# TicTacToe_v3.net
KiCad netlist of a schematic drawn in EAGLE
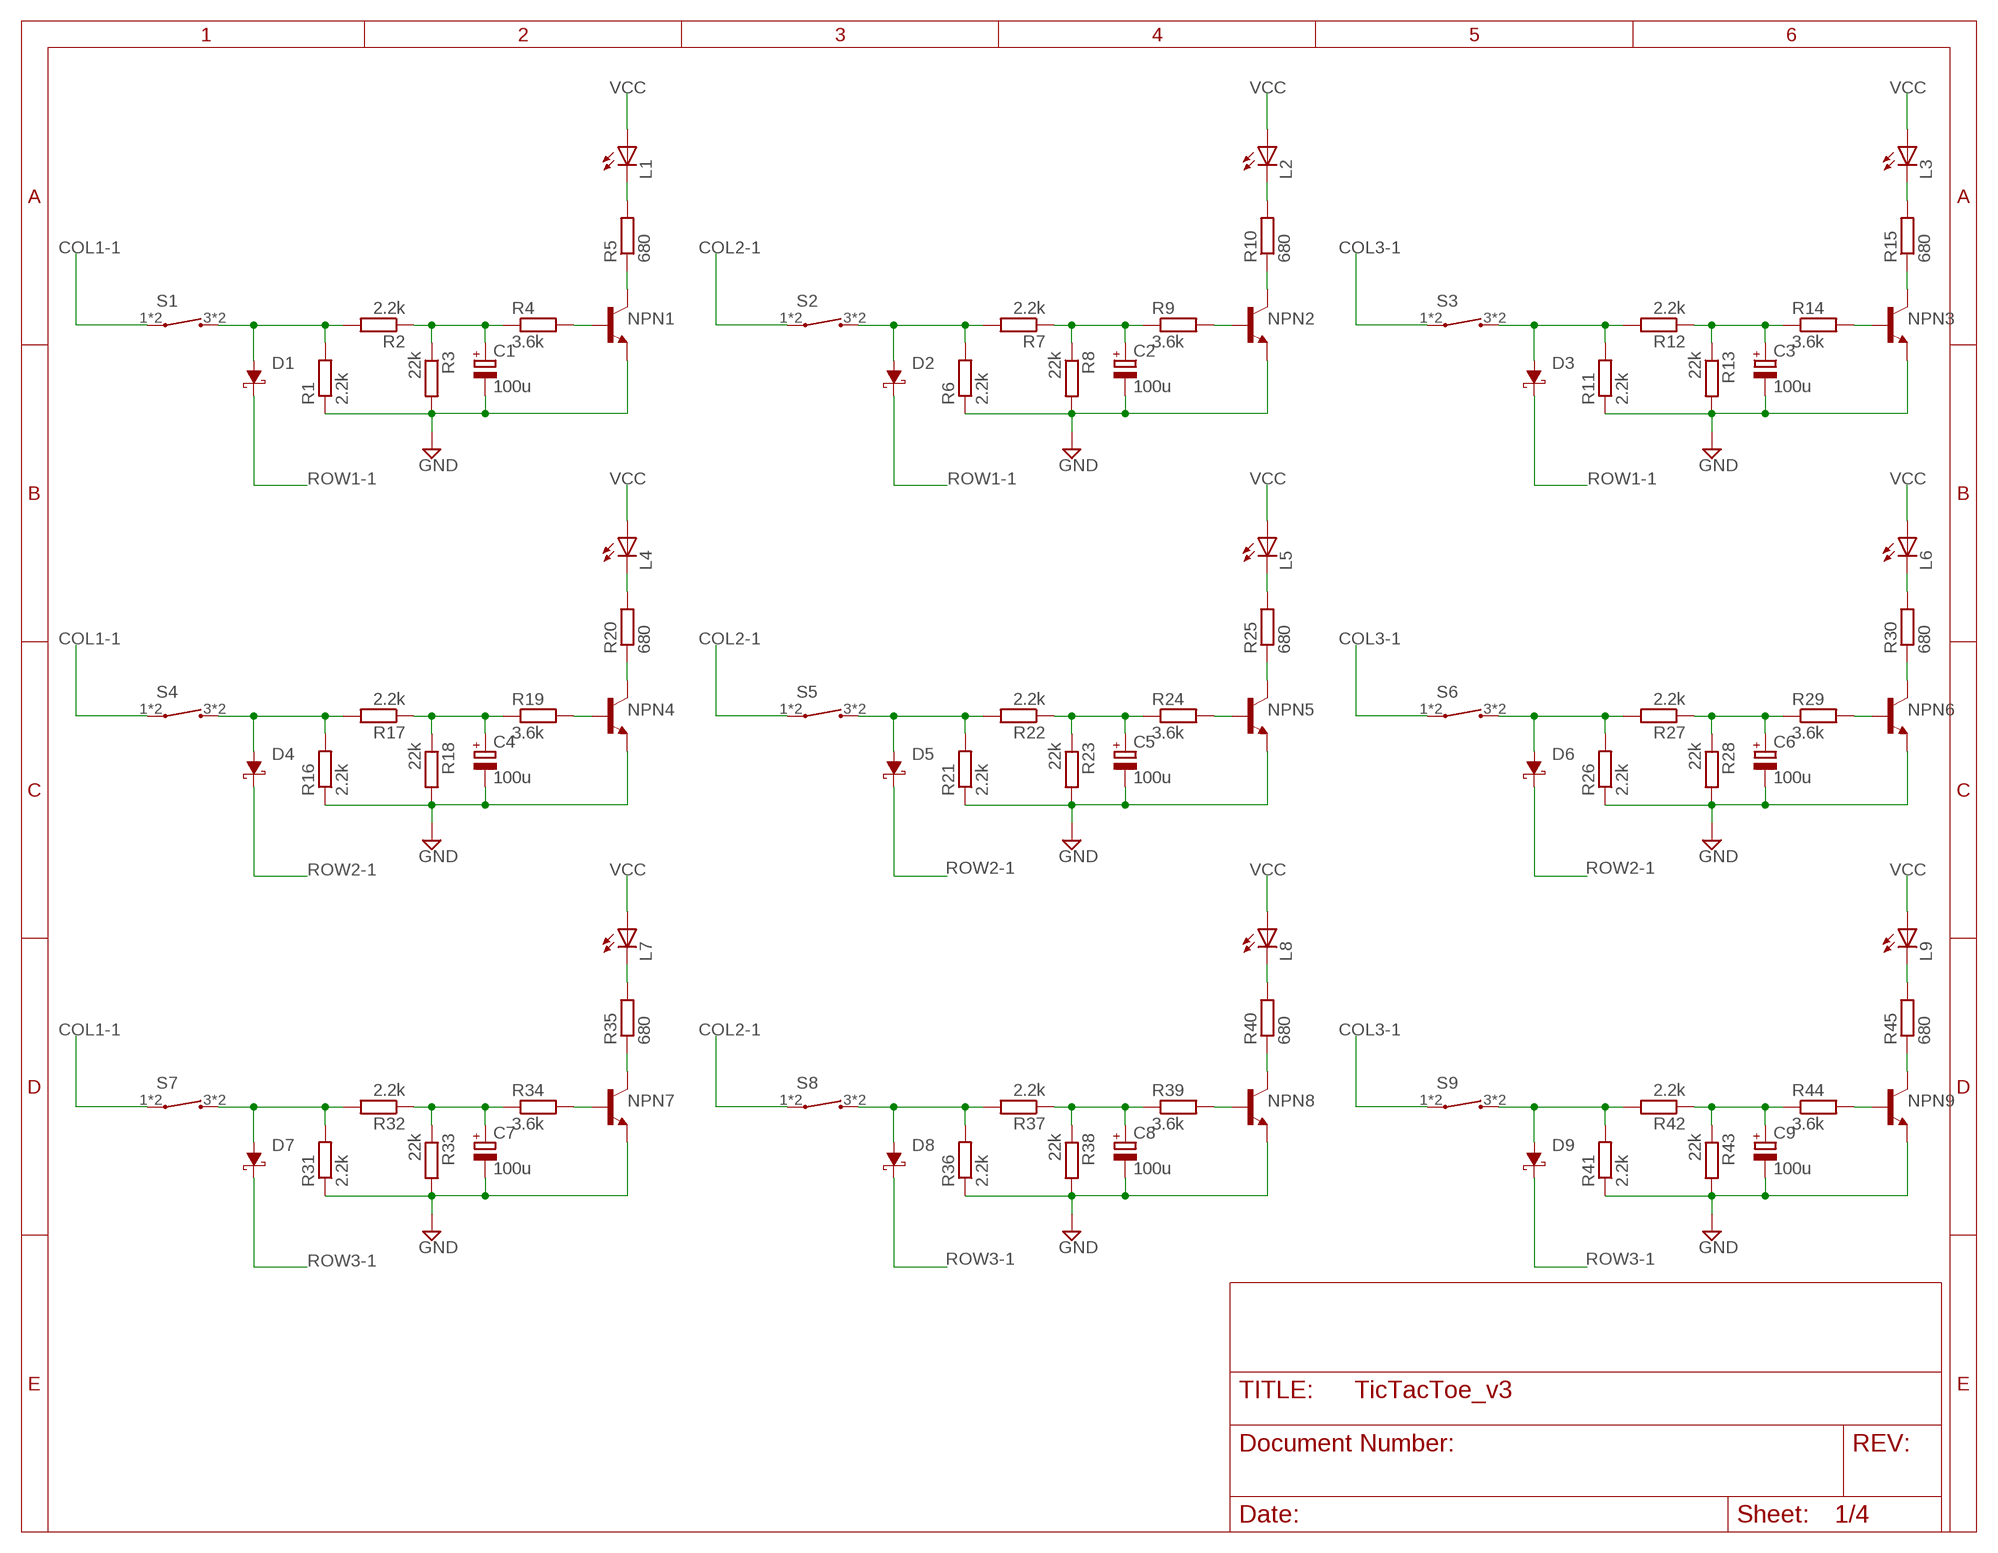
[diagram p0: schematic, sheet 1]
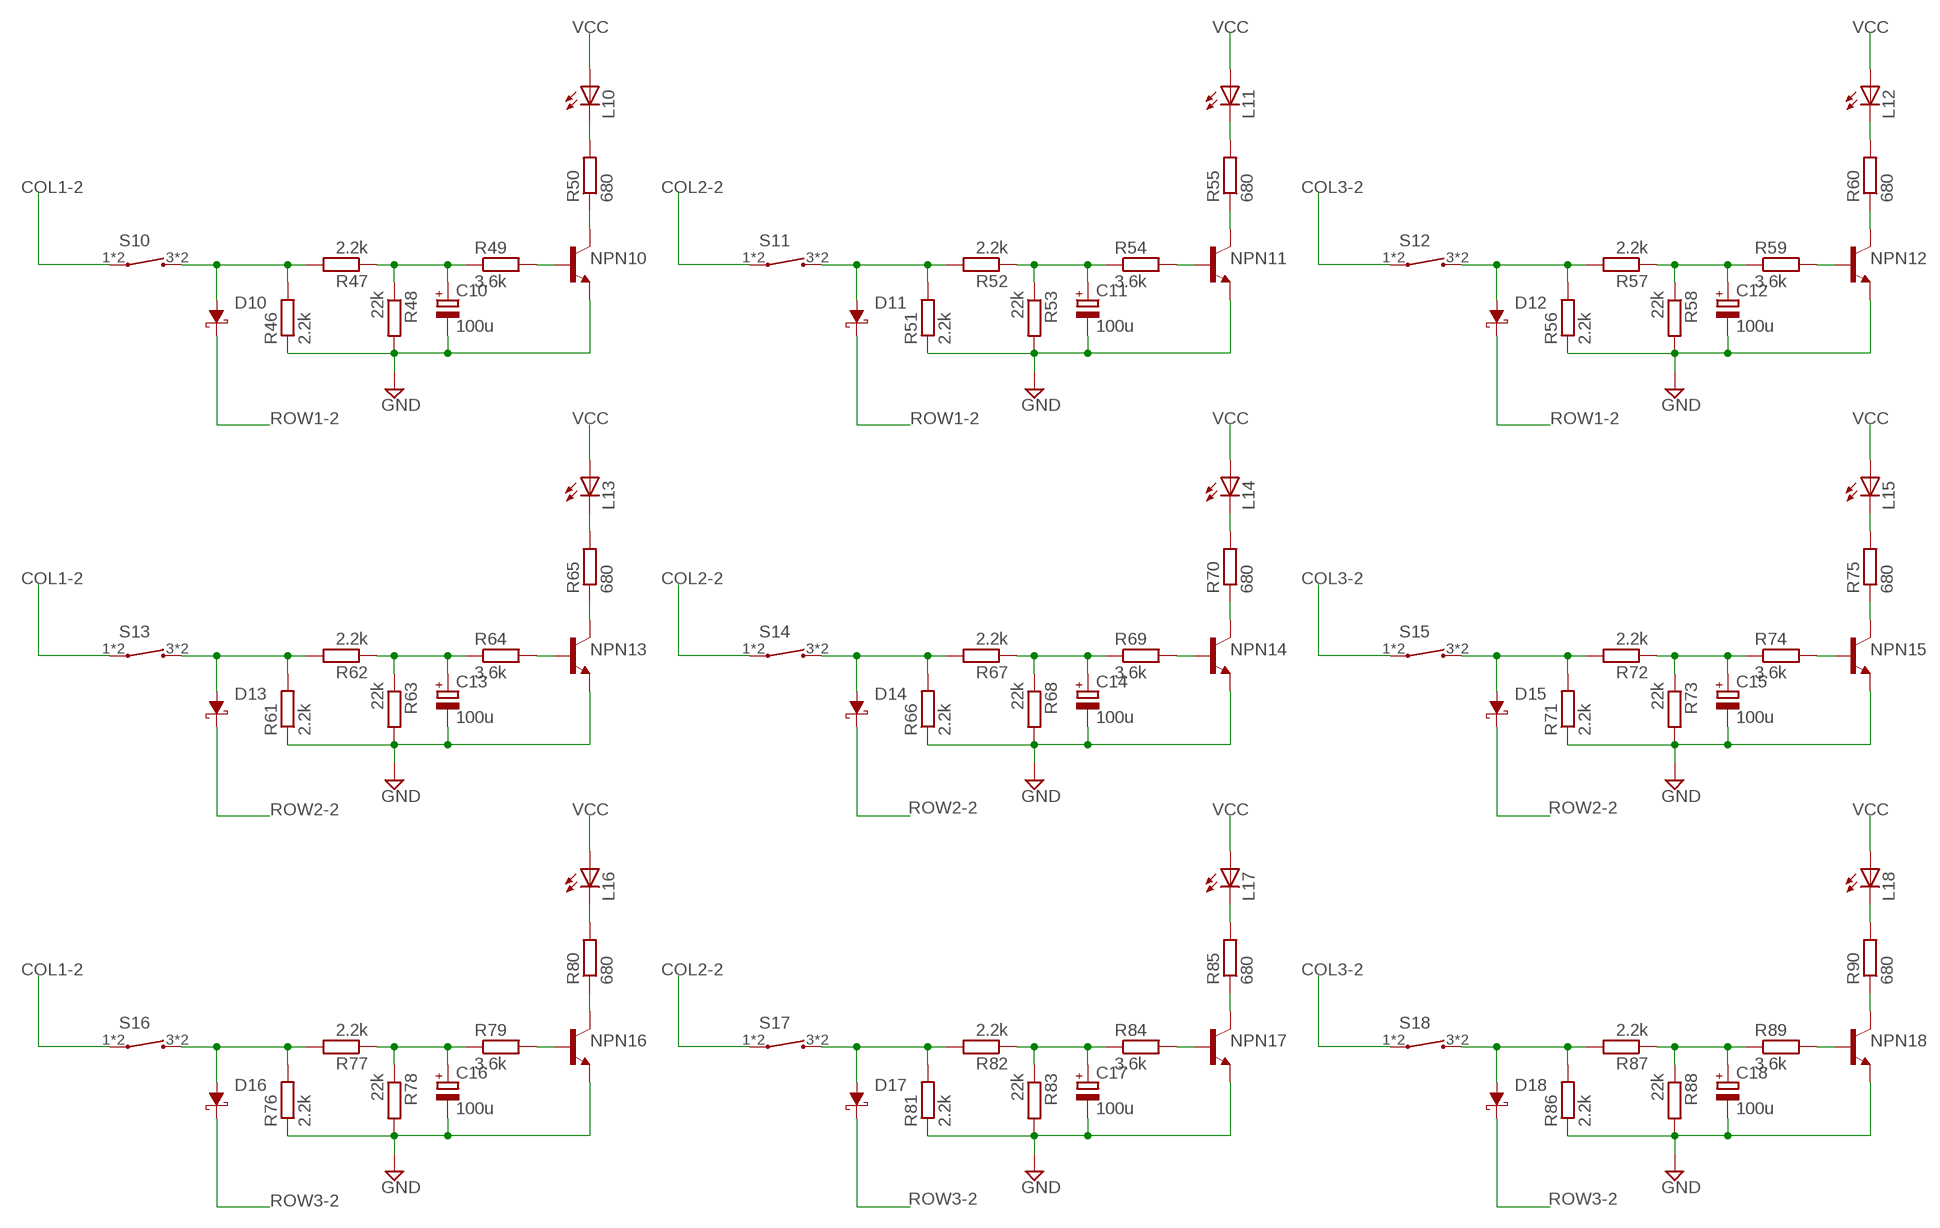
[diagram p1: schematic, sheet 2]
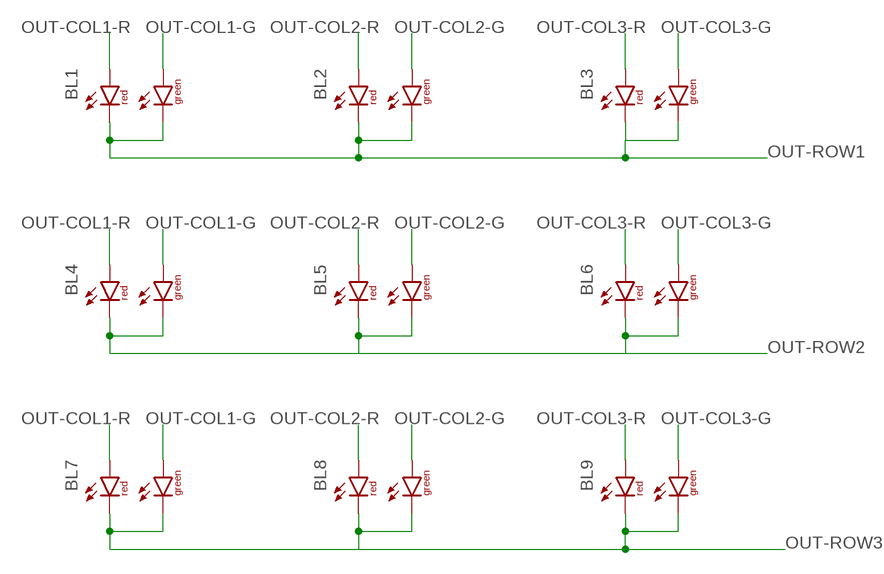
[diagram p2: schematic, sheet 3]
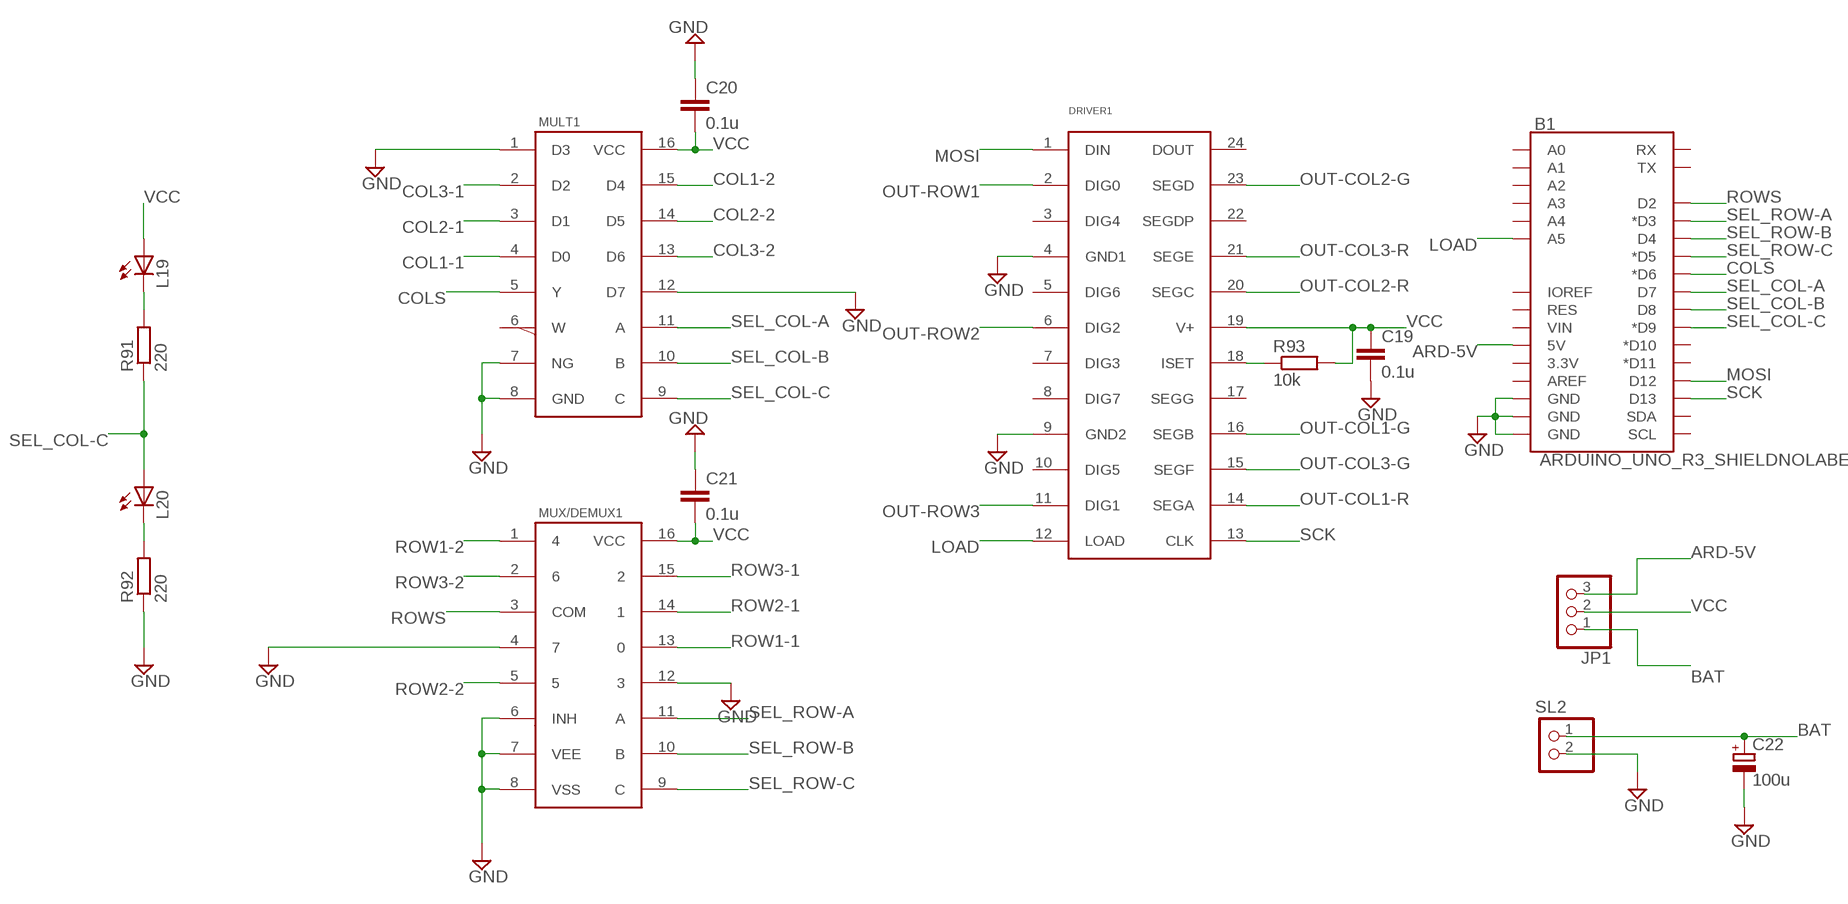
[diagram p3: schematic, sheet 4]

(export (version "E")
  (design (tool "Eeschema 10.0.6"))
  (components
    (comp (ref "BL1")
      (value "APHBM2012ETSGT(R/G)")
      (footprint "eagle-import:APHBM2012ETSGTC-BICOLORLED(R_G)")
      (libsource (lib "eagle-import") (part "APHBM2012ETSGT(R/G)"))
    )
    (comp (ref "BL2")
      (value "APHBM2012ETSGT(R/G)")
      (footprint "eagle-import:APHBM2012ETSGTC-BICOLORLED(R_G)")
      (libsource (lib "eagle-import") (part "APHBM2012ETSGT(R/G)"))
    )
    (comp (ref "BL3")
      (value "APHBM2012ETSGT(R/G)")
      (footprint "eagle-import:APHBM2012ETSGTC-BICOLORLED(R_G)")
      (libsource (lib "eagle-import") (part "APHBM2012ETSGT(R/G)"))
    )
    (comp (ref "BL4")
      (value "APHBM2012ETSGT(R/G)")
      (footprint "eagle-import:APHBM2012ETSGTC-BICOLORLED(R_G)")
      (libsource (lib "eagle-import") (part "APHBM2012ETSGT(R/G)"))
    )
    (comp (ref "BL5")
      (value "APHBM2012ETSGT(R/G)")
      (footprint "eagle-import:APHBM2012ETSGTC-BICOLORLED(R_G)")
      (libsource (lib "eagle-import") (part "APHBM2012ETSGT(R/G)"))
    )
    (comp (ref "BL6")
      (value "APHBM2012ETSGT(R/G)")
      (footprint "eagle-import:APHBM2012ETSGTC-BICOLORLED(R_G)")
      (libsource (lib "eagle-import") (part "APHBM2012ETSGT(R/G)"))
    )
    (comp (ref "BL7")
      (value "APHBM2012ETSGT(R/G)")
      (footprint "eagle-import:APHBM2012ETSGTC-BICOLORLED(R_G)")
      (libsource (lib "eagle-import") (part "APHBM2012ETSGT(R/G)"))
    )
    (comp (ref "BL8")
      (value "APHBM2012ETSGT(R/G)")
      (footprint "eagle-import:APHBM2012ETSGTC-BICOLORLED(R_G)")
      (libsource (lib "eagle-import") (part "APHBM2012ETSGT(R/G)"))
    )
    (comp (ref "BL9")
      (value "APHBM2012ETSGT(R/G)")
      (footprint "eagle-import:APHBM2012ETSGTC-BICOLORLED(R_G)")
      (libsource (lib "eagle-import") (part "APHBM2012ETSGT(R/G)"))
    )
    (comp (ref "C10")
      (value "100u")
      (footprint "eagle-import:T490A-COND")
      (libsource (lib "eagle-import") (part "T490A"))
    )
    (comp (ref "C11")
      (value "100u")
      (footprint "eagle-import:T490A-COND")
      (libsource (lib "eagle-import") (part "T490A"))
    )
    (comp (ref "C12")
      (value "100u")
      (footprint "eagle-import:T490A-COND")
      (libsource (lib "eagle-import") (part "T490A"))
    )
    (comp (ref "C13")
      (value "100u")
      (footprint "eagle-import:T490A-COND")
      (libsource (lib "eagle-import") (part "T490A"))
    )
    (comp (ref "C14")
      (value "100u")
      (footprint "eagle-import:T490A-COND")
      (libsource (lib "eagle-import") (part "T490A"))
    )
    (comp (ref "C15")
      (value "100u")
      (footprint "eagle-import:T490A-COND")
      (libsource (lib "eagle-import") (part "T490A"))
    )
    (comp (ref "C16")
      (value "100u")
      (footprint "eagle-import:T490A-COND")
      (libsource (lib "eagle-import") (part "T490A"))
    )
    (comp (ref "C17")
      (value "100u")
      (footprint "eagle-import:T490A-COND")
      (libsource (lib "eagle-import") (part "T490A"))
    )
    (comp (ref "C18")
      (value "100u")
      (footprint "eagle-import:T490A-COND")
      (libsource (lib "eagle-import") (part "T490A"))
    )
    (comp (ref "D10")
      (value "PMEG3010EH")
      (footprint "eagle-import:PMEG3010EH-SCHOTTKYDIODE")
      (libsource (lib "eagle-import") (part "PMEG3010EH"))
    )
    (comp (ref "D11")
      (value "PMEG3010EH")
      (footprint "eagle-import:PMEG3010EH-SCHOTTKYDIODE")
      (libsource (lib "eagle-import") (part "PMEG3010EH"))
    )
    (comp (ref "D12")
      (value "PMEG3010EH")
      (footprint "eagle-import:PMEG3010EH-SCHOTTKYDIODE")
      (libsource (lib "eagle-import") (part "PMEG3010EH"))
    )
    (comp (ref "D13")
      (value "PMEG3010EH")
      (footprint "eagle-import:PMEG3010EH-SCHOTTKYDIODE")
      (libsource (lib "eagle-import") (part "PMEG3010EH"))
    )
    (comp (ref "D14")
      (value "PMEG3010EH")
      (footprint "eagle-import:PMEG3010EH-SCHOTTKYDIODE")
      (libsource (lib "eagle-import") (part "PMEG3010EH"))
    )
    (comp (ref "D15")
      (value "PMEG3010EH")
      (footprint "eagle-import:PMEG3010EH-SCHOTTKYDIODE")
      (libsource (lib "eagle-import") (part "PMEG3010EH"))
    )
    (comp (ref "D16")
      (value "PMEG3010EH")
      (footprint "eagle-import:PMEG3010EH-SCHOTTKYDIODE")
      (libsource (lib "eagle-import") (part "PMEG3010EH"))
    )
    (comp (ref "D17")
      (value "PMEG3010EH")
      (footprint "eagle-import:PMEG3010EH-SCHOTTKYDIODE")
      (libsource (lib "eagle-import") (part "PMEG3010EH"))
    )
    (comp (ref "D18")
      (value "PMEG3010EH")
      (footprint "eagle-import:PMEG3010EH-SCHOTTKYDIODE")
      (libsource (lib "eagle-import") (part "PMEG3010EH"))
    )
    (comp (ref "L10")
      (value "150060BS75003")
      (footprint "eagle-import:WL-SMCW-LED(BLUE)")
      (libsource (lib "eagle-import") (part "150060BS75003"))
    )
    (comp (ref "L11")
      (value "150060BS75003")
      (footprint "eagle-import:WL-SMCW-LED(BLUE)")
      (libsource (lib "eagle-import") (part "150060BS75003"))
    )
    (comp (ref "L12")
      (value "150060BS75003")
      (footprint "eagle-import:WL-SMCW-LED(BLUE)")
      (libsource (lib "eagle-import") (part "150060BS75003"))
    )
    (comp (ref "L13")
      (value "150060BS75003")
      (footprint "eagle-import:WL-SMCW-LED(BLUE)")
      (libsource (lib "eagle-import") (part "150060BS75003"))
    )
    (comp (ref "L14")
      (value "150060BS75003")
      (footprint "eagle-import:WL-SMCW-LED(BLUE)")
      (libsource (lib "eagle-import") (part "150060BS75003"))
    )
    (comp (ref "L15")
      (value "150060BS75003")
      (footprint "eagle-import:WL-SMCW-LED(BLUE)")
      (libsource (lib "eagle-import") (part "150060BS75003"))
    )
    (comp (ref "L16")
      (value "150060BS75003")
      (footprint "eagle-import:WL-SMCW-LED(BLUE)")
      (libsource (lib "eagle-import") (part "150060BS75003"))
    )
    (comp (ref "L17")
      (value "150060BS75003")
      (footprint "eagle-import:WL-SMCW-LED(BLUE)")
      (libsource (lib "eagle-import") (part "150060BS75003"))
    )
    (comp (ref "L18")
      (value "150060BS75003")
      (footprint "eagle-import:WL-SMCW-LED(BLUE)")
      (libsource (lib "eagle-import") (part "150060BS75003"))
    )
    (comp (ref "NPN10")
      (value "BC848")
      (footprint "eagle-import:BC848-NPN")
      (libsource (lib "eagle-import") (part "BC848"))
    )
    (comp (ref "NPN11")
      (value "BC848")
      (footprint "eagle-import:BC848-NPN")
      (libsource (lib "eagle-import") (part "BC848"))
    )
    (comp (ref "NPN12")
      (value "BC848")
      (footprint "eagle-import:BC848-NPN")
      (libsource (lib "eagle-import") (part "BC848"))
    )
    (comp (ref "NPN13")
      (value "BC848")
      (footprint "eagle-import:BC848-NPN")
      (libsource (lib "eagle-import") (part "BC848"))
    )
    (comp (ref "NPN14")
      (value "BC848")
      (footprint "eagle-import:BC848-NPN")
      (libsource (lib "eagle-import") (part "BC848"))
    )
    (comp (ref "NPN15")
      (value "BC848")
      (footprint "eagle-import:BC848-NPN")
      (libsource (lib "eagle-import") (part "BC848"))
    )
    (comp (ref "NPN16")
      (value "BC848")
      (footprint "eagle-import:BC848-NPN")
      (libsource (lib "eagle-import") (part "BC848"))
    )
    (comp (ref "NPN17")
      (value "BC848")
      (footprint "eagle-import:BC848-NPN")
      (libsource (lib "eagle-import") (part "BC848"))
    )
    (comp (ref "NPN18")
      (value "BC848")
      (footprint "eagle-import:BC848-NPN")
      (libsource (lib "eagle-import") (part "BC848"))
    )
    (comp (ref "R46")
      (value "2.2k")
      (footprint "eagle-import:R0603")
      (libsource (lib "eagle-import") (part "R-EU_R0603"))
    )
    (comp (ref "R47")
      (value "2.2k")
      (footprint "eagle-import:R0603")
      (libsource (lib "eagle-import") (part "R-EU_R0603"))
    )
    (comp (ref "R48")
      (value "22k")
      (footprint "eagle-import:R0603")
      (libsource (lib "eagle-import") (part "R-EU_R0603"))
    )
    (comp (ref "R49")
      (value "3.6k")
      (footprint "eagle-import:R0603")
      (libsource (lib "eagle-import") (part "R-EU_R0603"))
    )
    (comp (ref "R50")
      (value "680")
      (footprint "eagle-import:R0603")
      (libsource (lib "eagle-import") (part "R-EU_R0603"))
    )
    (comp (ref "R51")
      (value "2.2k")
      (footprint "eagle-import:R0603")
      (libsource (lib "eagle-import") (part "R-EU_R0603"))
    )
    (comp (ref "R52")
      (value "2.2k")
      (footprint "eagle-import:R0603")
      (libsource (lib "eagle-import") (part "R-EU_R0603"))
    )
    (comp (ref "R53")
      (value "22k")
      (footprint "eagle-import:R0603")
      (libsource (lib "eagle-import") (part "R-EU_R0603"))
    )
    (comp (ref "R54")
      (value "3.6k")
      (footprint "eagle-import:R0603")
      (libsource (lib "eagle-import") (part "R-EU_R0603"))
    )
    (comp (ref "R55")
      (value "680")
      (footprint "eagle-import:R0603")
      (libsource (lib "eagle-import") (part "R-EU_R0603"))
    )
    (comp (ref "R56")
      (value "2.2k")
      (footprint "eagle-import:R0603")
      (libsource (lib "eagle-import") (part "R-EU_R0603"))
    )
    (comp (ref "R57")
      (value "2.2k")
      (footprint "eagle-import:R0603")
      (libsource (lib "eagle-import") (part "R-EU_R0603"))
    )
    (comp (ref "R58")
      (value "22k")
      (footprint "eagle-import:R0603")
      (libsource (lib "eagle-import") (part "R-EU_R0603"))
    )
    (comp (ref "R59")
      (value "3.6k")
      (footprint "eagle-import:R0603")
      (libsource (lib "eagle-import") (part "R-EU_R0603"))
    )
    (comp (ref "R60")
      (value "680")
      (footprint "eagle-import:R0603")
      (libsource (lib "eagle-import") (part "R-EU_R0603"))
    )
    (comp (ref "R61")
      (value "2.2k")
      (footprint "eagle-import:R0603")
      (libsource (lib "eagle-import") (part "R-EU_R0603"))
    )
    (comp (ref "R62")
      (value "2.2k")
      (footprint "eagle-import:R0603")
      (libsource (lib "eagle-import") (part "R-EU_R0603"))
    )
    (comp (ref "R63")
      (value "22k")
      (footprint "eagle-import:R0603")
      (libsource (lib "eagle-import") (part "R-EU_R0603"))
    )
    (comp (ref "R64")
      (value "3.6k")
      (footprint "eagle-import:R0603")
      (libsource (lib "eagle-import") (part "R-EU_R0603"))
    )
    (comp (ref "R65")
      (value "680")
      (footprint "eagle-import:R0603")
      (libsource (lib "eagle-import") (part "R-EU_R0603"))
    )
    (comp (ref "R66")
      (value "2.2k")
      (footprint "eagle-import:R0603")
      (libsource (lib "eagle-import") (part "R-EU_R0603"))
    )
    (comp (ref "R67")
      (value "2.2k")
      (footprint "eagle-import:R0603")
      (libsource (lib "eagle-import") (part "R-EU_R0603"))
    )
    (comp (ref "R68")
      (value "22k")
      (footprint "eagle-import:R0603")
      (libsource (lib "eagle-import") (part "R-EU_R0603"))
    )
    (comp (ref "R69")
      (value "3.6k")
      (footprint "eagle-import:R0603")
      (libsource (lib "eagle-import") (part "R-EU_R0603"))
    )
    (comp (ref "R70")
      (value "680")
      (footprint "eagle-import:R0603")
      (libsource (lib "eagle-import") (part "R-EU_R0603"))
    )
    (comp (ref "R71")
      (value "2.2k")
      (footprint "eagle-import:R0603")
      (libsource (lib "eagle-import") (part "R-EU_R0603"))
    )
    (comp (ref "R72")
      (value "2.2k")
      (footprint "eagle-import:R0603")
      (libsource (lib "eagle-import") (part "R-EU_R0603"))
    )
    (comp (ref "R73")
      (value "22k")
      (footprint "eagle-import:R0603")
      (libsource (lib "eagle-import") (part "R-EU_R0603"))
    )
    (comp (ref "R74")
      (value "3.6k")
      (footprint "eagle-import:R0603")
      (libsource (lib "eagle-import") (part "R-EU_R0603"))
    )
    (comp (ref "R75")
      (value "680")
      (footprint "eagle-import:R0603")
      (libsource (lib "eagle-import") (part "R-EU_R0603"))
    )
    (comp (ref "R76")
      (value "2.2k")
      (footprint "eagle-import:R0603")
      (libsource (lib "eagle-import") (part "R-EU_R0603"))
    )
    (comp (ref "R77")
      (value "2.2k")
      (footprint "eagle-import:R0603")
      (libsource (lib "eagle-import") (part "R-EU_R0603"))
    )
    (comp (ref "R78")
      (value "22k")
      (footprint "eagle-import:R0603")
      (libsource (lib "eagle-import") (part "R-EU_R0603"))
    )
    (comp (ref "R79")
      (value "3.6k")
      (footprint "eagle-import:R0603")
      (libsource (lib "eagle-import") (part "R-EU_R0603"))
    )
    (comp (ref "R80")
      (value "680")
      (footprint "eagle-import:R0603")
      (libsource (lib "eagle-import") (part "R-EU_R0603"))
    )
    (comp (ref "R81")
      (value "2.2k")
      (footprint "eagle-import:R0603")
      (libsource (lib "eagle-import") (part "R-EU_R0603"))
    )
    (comp (ref "R82")
      (value "2.2k")
      (footprint "eagle-import:R0603")
      (libsource (lib "eagle-import") (part "R-EU_R0603"))
    )
    (comp (ref "R83")
      (value "22k")
      (footprint "eagle-import:R0603")
      (libsource (lib "eagle-import") (part "R-EU_R0603"))
    )
    (comp (ref "R84")
      (value "3.6k")
      (footprint "eagle-import:R0603")
      (libsource (lib "eagle-import") (part "R-EU_R0603"))
    )
    (comp (ref "R85")
      (value "680")
      (footprint "eagle-import:R0603")
      (libsource (lib "eagle-import") (part "R-EU_R0603"))
    )
    (comp (ref "R86")
      (value "2.2k")
      (footprint "eagle-import:R0603")
      (libsource (lib "eagle-import") (part "R-EU_R0603"))
    )
    (comp (ref "R87")
      (value "2.2k")
      (footprint "eagle-import:R0603")
      (libsource (lib "eagle-import") (part "R-EU_R0603"))
    )
    (comp (ref "R88")
      (value "22k")
      (footprint "eagle-import:R0603")
      (libsource (lib "eagle-import") (part "R-EU_R0603"))
    )
    (comp (ref "R89")
      (value "3.6k")
      (footprint "eagle-import:R0603")
      (libsource (lib "eagle-import") (part "R-EU_R0603"))
    )
    (comp (ref "R90")
      (value "680")
      (footprint "eagle-import:R0603")
      (libsource (lib "eagle-import") (part "R-EU_R0603"))
    )
    (comp (ref "S10")
      (value "PTS647")
      (footprint "eagle-import:PTS647-TACTSWITCH")
      (libsource (lib "eagle-import") (part "PTS647"))
    )
    (comp (ref "S11")
      (value "PTS647")
      (footprint "eagle-import:PTS647-TACTSWITCH")
      (libsource (lib "eagle-import") (part "PTS647"))
    )
    (comp (ref "S12")
      (value "PTS647")
      (footprint "eagle-import:PTS647-TACTSWITCH")
      (libsource (lib "eagle-import") (part "PTS647"))
    )
    (comp (ref "S13")
      (value "PTS647")
      (footprint "eagle-import:PTS647-TACTSWITCH")
      (libsource (lib "eagle-import") (part "PTS647"))
    )
    (comp (ref "S14")
      (value "PTS647")
      (footprint "eagle-import:PTS647-TACTSWITCH")
      (libsource (lib "eagle-import") (part "PTS647"))
    )
    (comp (ref "S15")
      (value "PTS647")
      (footprint "eagle-import:PTS647-TACTSWITCH")
      (libsource (lib "eagle-import") (part "PTS647"))
    )
    (comp (ref "S16")
      (value "PTS647")
      (footprint "eagle-import:PTS647-TACTSWITCH")
      (libsource (lib "eagle-import") (part "PTS647"))
    )
    (comp (ref "S17")
      (value "PTS647")
      (footprint "eagle-import:PTS647-TACTSWITCH")
      (libsource (lib "eagle-import") (part "PTS647"))
    )
    (comp (ref "S18")
      (value "PTS647")
      (footprint "eagle-import:PTS647-TACTSWITCH")
      (libsource (lib "eagle-import") (part "PTS647"))
    )
    (comp (ref "B1")
      (value "ARDUINO_UNO_R3_SHIELDNOLABELS")
      (footprint "eagle-import:UNO_R3_SHIELD_NOLABELS")
      (libsource (lib "eagle-import") (part "ARDUINO_UNO_R3_SHIELDNOLABELS"))
    )
    (comp (ref "C19")
      (value "0.1u")
      (footprint "eagle-import:C0603")
      (libsource (lib "eagle-import") (part "C-EUC0603"))
    )
    (comp (ref "C20")
      (value "0.1u")
      (footprint "eagle-import:C0603")
      (libsource (lib "eagle-import") (part "C-EUC0603"))
    )
    (comp (ref "C21")
      (value "0.1u")
      (footprint "eagle-import:C0603")
      (libsource (lib "eagle-import") (part "C-EUC0603"))
    )
    (comp (ref "C22")
      (value "100u")
      (footprint "eagle-import:T490A-COND")
      (libsource (lib "eagle-import") (part "T490A"))
    )
    (comp (ref "DRIVER1")
      (value "MAX7219")
      (footprint "eagle-import:MAX7219EWGT")
      (libsource (lib "eagle-import") (part "MAX7219"))
    )
    (comp (ref "JP1")
      (value "PINHD-1X3")
      (footprint "eagle-import:1X03")
      (libsource (lib "eagle-import") (part "PINHD-1X3"))
    )
    (comp (ref "L19")
      (value "150060BS75003")
      (footprint "eagle-import:WL-SMCW-LED(BLUE)")
      (libsource (lib "eagle-import") (part "150060BS75003"))
    )
    (comp (ref "L20")
      (value "150060BS75003")
      (footprint "eagle-import:WL-SMCW-LED(BLUE)")
      (libsource (lib "eagle-import") (part "150060BS75003"))
    )
    (comp (ref "MULT1")
      (value "SN74F151BDR")
      (footprint "eagle-import:SOIC16N")
      (libsource (lib "eagle-import") (part "SN74F151BDR"))
    )
    (comp (ref "MUX/DEMUX1")
      (value "TC4051B")
      (footprint "eagle-import:SOIC16N")
      (libsource (lib "eagle-import") (part "TC4051B"))
    )
    (comp (ref "R91")
      (value "220")
      (footprint "eagle-import:R0603")
      (libsource (lib "eagle-import") (part "R-EU_R0603"))
    )
    (comp (ref "R92")
      (value "220")
      (footprint "eagle-import:R0603")
      (libsource (lib "eagle-import") (part "R-EU_R0603"))
    )
    (comp (ref "R93")
      (value "10k")
      (footprint "eagle-import:R0603")
      (libsource (lib "eagle-import") (part "R-EU_R0603"))
    )
    (comp (ref "SL2")
      (value "PINHD-1X2")
      (footprint "eagle-import:1X02")
      (libsource (lib "eagle-import") (part "PINHD-1X2"))
    )
    (comp (ref "C1")
      (value "100u")
      (footprint "eagle-import:T490A-COND")
      (libsource (lib "eagle-import") (part "T490A"))
    )
    (comp (ref "C2")
      (value "100u")
      (footprint "eagle-import:T490A-COND")
      (libsource (lib "eagle-import") (part "T490A"))
    )
    (comp (ref "C3")
      (value "100u")
      (footprint "eagle-import:T490A-COND")
      (libsource (lib "eagle-import") (part "T490A"))
    )
    (comp (ref "C4")
      (value "100u")
      (footprint "eagle-import:T490A-COND")
      (libsource (lib "eagle-import") (part "T490A"))
    )
    (comp (ref "C5")
      (value "100u")
      (footprint "eagle-import:T490A-COND")
      (libsource (lib "eagle-import") (part "T490A"))
    )
    (comp (ref "C6")
      (value "100u")
      (footprint "eagle-import:T490A-COND")
      (libsource (lib "eagle-import") (part "T490A"))
    )
    (comp (ref "C7")
      (value "100u")
      (footprint "eagle-import:T490A-COND")
      (libsource (lib "eagle-import") (part "T490A"))
    )
    (comp (ref "C8")
      (value "100u")
      (footprint "eagle-import:T490A-COND")
      (libsource (lib "eagle-import") (part "T490A"))
    )
    (comp (ref "C9")
      (value "100u")
      (footprint "eagle-import:T490A-COND")
      (libsource (lib "eagle-import") (part "T490A"))
    )
    (comp (ref "D1")
      (value "PMEG3010EH")
      (footprint "eagle-import:PMEG3010EH-SCHOTTKYDIODE")
      (libsource (lib "eagle-import") (part "PMEG3010EH"))
    )
    (comp (ref "D2")
      (value "PMEG3010EH")
      (footprint "eagle-import:PMEG3010EH-SCHOTTKYDIODE")
      (libsource (lib "eagle-import") (part "PMEG3010EH"))
    )
    (comp (ref "D3")
      (value "PMEG3010EH")
      (footprint "eagle-import:PMEG3010EH-SCHOTTKYDIODE")
      (libsource (lib "eagle-import") (part "PMEG3010EH"))
    )
    (comp (ref "D4")
      (value "PMEG3010EH")
      (footprint "eagle-import:PMEG3010EH-SCHOTTKYDIODE")
      (libsource (lib "eagle-import") (part "PMEG3010EH"))
    )
    (comp (ref "D5")
      (value "PMEG3010EH")
      (footprint "eagle-import:PMEG3010EH-SCHOTTKYDIODE")
      (libsource (lib "eagle-import") (part "PMEG3010EH"))
    )
    (comp (ref "D6")
      (value "PMEG3010EH")
      (footprint "eagle-import:PMEG3010EH-SCHOTTKYDIODE")
      (libsource (lib "eagle-import") (part "PMEG3010EH"))
    )
    (comp (ref "D7")
      (value "PMEG3010EH")
      (footprint "eagle-import:PMEG3010EH-SCHOTTKYDIODE")
      (libsource (lib "eagle-import") (part "PMEG3010EH"))
    )
    (comp (ref "D8")
      (value "PMEG3010EH")
      (footprint "eagle-import:PMEG3010EH-SCHOTTKYDIODE")
      (libsource (lib "eagle-import") (part "PMEG3010EH"))
    )
    (comp (ref "D9")
      (value "PMEG3010EH")
      (footprint "eagle-import:PMEG3010EH-SCHOTTKYDIODE")
      (libsource (lib "eagle-import") (part "PMEG3010EH"))
    )
    (comp (ref "L1")
      (value "150060BS75003")
      (footprint "eagle-import:WL-SMCW-LED(BLUE)")
      (libsource (lib "eagle-import") (part "150060BS75003"))
    )
    (comp (ref "L2")
      (value "150060BS75003")
      (footprint "eagle-import:WL-SMCW-LED(BLUE)")
      (libsource (lib "eagle-import") (part "150060BS75003"))
    )
    (comp (ref "L3")
      (value "150060BS75003")
      (footprint "eagle-import:WL-SMCW-LED(BLUE)")
      (libsource (lib "eagle-import") (part "150060BS75003"))
    )
    (comp (ref "L4")
      (value "150060BS75003")
      (footprint "eagle-import:WL-SMCW-LED(BLUE)")
      (libsource (lib "eagle-import") (part "150060BS75003"))
    )
    (comp (ref "L5")
      (value "150060BS75003")
      (footprint "eagle-import:WL-SMCW-LED(BLUE)")
      (libsource (lib "eagle-import") (part "150060BS75003"))
    )
    (comp (ref "L6")
      (value "150060BS75003")
      (footprint "eagle-import:WL-SMCW-LED(BLUE)")
      (libsource (lib "eagle-import") (part "150060BS75003"))
    )
    (comp (ref "L7")
      (value "150060BS75003")
      (footprint "eagle-import:WL-SMCW-LED(BLUE)")
      (libsource (lib "eagle-import") (part "150060BS75003"))
    )
    (comp (ref "L8")
      (value "150060BS75003")
      (footprint "eagle-import:WL-SMCW-LED(BLUE)")
      (libsource (lib "eagle-import") (part "150060BS75003"))
    )
    (comp (ref "L9")
      (value "150060BS75003")
      (footprint "eagle-import:WL-SMCW-LED(BLUE)")
      (libsource (lib "eagle-import") (part "150060BS75003"))
    )
    (comp (ref "NPN1")
      (value "BC848")
      (footprint "eagle-import:BC848-NPN")
      (libsource (lib "eagle-import") (part "BC848"))
    )
    (comp (ref "NPN2")
      (value "BC848")
      (footprint "eagle-import:BC848-NPN")
      (libsource (lib "eagle-import") (part "BC848"))
    )
    (comp (ref "NPN3")
      (value "BC848")
      (footprint "eagle-import:BC848-NPN")
      (libsource (lib "eagle-import") (part "BC848"))
    )
    (comp (ref "NPN4")
      (value "BC848")
      (footprint "eagle-import:BC848-NPN")
      (libsource (lib "eagle-import") (part "BC848"))
    )
    (comp (ref "NPN5")
      (value "BC848")
      (footprint "eagle-import:BC848-NPN")
      (libsource (lib "eagle-import") (part "BC848"))
    )
    (comp (ref "NPN6")
      (value "BC848")
      (footprint "eagle-import:BC848-NPN")
      (libsource (lib "eagle-import") (part "BC848"))
    )
    (comp (ref "NPN7")
      (value "BC848")
      (footprint "eagle-import:BC848-NPN")
      (libsource (lib "eagle-import") (part "BC848"))
    )
    (comp (ref "NPN8")
      (value "BC848")
      (footprint "eagle-import:BC848-NPN")
      (libsource (lib "eagle-import") (part "BC848"))
    )
    (comp (ref "NPN9")
      (value "BC848")
      (footprint "eagle-import:BC848-NPN")
      (libsource (lib "eagle-import") (part "BC848"))
    )
    (comp (ref "R1")
      (value "2.2k")
      (footprint "eagle-import:R0603")
      (libsource (lib "eagle-import") (part "R-EU_R0603"))
    )
    (comp (ref "R2")
      (value "2.2k")
      (footprint "eagle-import:R0603")
      (libsource (lib "eagle-import") (part "R-EU_R0603"))
    )
    (comp (ref "R3")
      (value "22k")
      (footprint "eagle-import:R0603")
      (libsource (lib "eagle-import") (part "R-EU_R0603"))
    )
    (comp (ref "R4")
      (value "3.6k")
      (footprint "eagle-import:R0603")
      (libsource (lib "eagle-import") (part "R-EU_R0603"))
    )
    (comp (ref "R5")
      (value "680")
      (footprint "eagle-import:R0603")
      (libsource (lib "eagle-import") (part "R-EU_R0603"))
    )
    (comp (ref "R6")
      (value "2.2k")
      (footprint "eagle-import:R0603")
      (libsource (lib "eagle-import") (part "R-EU_R0603"))
    )
    (comp (ref "R7")
      (value "2.2k")
      (footprint "eagle-import:R0603")
      (libsource (lib "eagle-import") (part "R-EU_R0603"))
    )
    (comp (ref "R8")
      (value "22k")
      (footprint "eagle-import:R0603")
      (libsource (lib "eagle-import") (part "R-EU_R0603"))
    )
    (comp (ref "R9")
      (value "3.6k")
      (footprint "eagle-import:R0603")
      (libsource (lib "eagle-import") (part "R-EU_R0603"))
    )
    (comp (ref "R10")
      (value "680")
      (footprint "eagle-import:R0603")
      (libsource (lib "eagle-import") (part "R-EU_R0603"))
    )
    (comp (ref "R11")
      (value "2.2k")
      (footprint "eagle-import:R0603")
      (libsource (lib "eagle-import") (part "R-EU_R0603"))
    )
    (comp (ref "R12")
      (value "2.2k")
      (footprint "eagle-import:R0603")
      (libsource (lib "eagle-import") (part "R-EU_R0603"))
    )
    (comp (ref "R13")
      (value "22k")
      (footprint "eagle-import:R0603")
      (libsource (lib "eagle-import") (part "R-EU_R0603"))
    )
    (comp (ref "R14")
      (value "3.6k")
      (footprint "eagle-import:R0603")
      (libsource (lib "eagle-import") (part "R-EU_R0603"))
    )
    (comp (ref "R15")
      (value "680")
      (footprint "eagle-import:R0603")
      (libsource (lib "eagle-import") (part "R-EU_R0603"))
    )
    (comp (ref "R16")
      (value "2.2k")
      (footprint "eagle-import:R0603")
      (libsource (lib "eagle-import") (part "R-EU_R0603"))
    )
    (comp (ref "R17")
      (value "2.2k")
      (footprint "eagle-import:R0603")
      (libsource (lib "eagle-import") (part "R-EU_R0603"))
    )
    (comp (ref "R18")
      (value "22k")
      (footprint "eagle-import:R0603")
      (libsource (lib "eagle-import") (part "R-EU_R0603"))
    )
    (comp (ref "R19")
      (value "3.6k")
      (footprint "eagle-import:R0603")
      (libsource (lib "eagle-import") (part "R-EU_R0603"))
    )
    (comp (ref "R20")
      (value "680")
      (footprint "eagle-import:R0603")
      (libsource (lib "eagle-import") (part "R-EU_R0603"))
    )
    (comp (ref "R21")
      (value "2.2k")
      (footprint "eagle-import:R0603")
      (libsource (lib "eagle-import") (part "R-EU_R0603"))
    )
    (comp (ref "R22")
      (value "2.2k")
      (footprint "eagle-import:R0603")
      (libsource (lib "eagle-import") (part "R-EU_R0603"))
    )
    (comp (ref "R23")
      (value "22k")
      (footprint "eagle-import:R0603")
      (libsource (lib "eagle-import") (part "R-EU_R0603"))
    )
    (comp (ref "R24")
      (value "3.6k")
      (footprint "eagle-import:R0603")
      (libsource (lib "eagle-import") (part "R-EU_R0603"))
    )
    (comp (ref "R25")
      (value "680")
      (footprint "eagle-import:R0603")
      (libsource (lib "eagle-import") (part "R-EU_R0603"))
    )
    (comp (ref "R26")
      (value "2.2k")
      (footprint "eagle-import:R0603")
      (libsource (lib "eagle-import") (part "R-EU_R0603"))
    )
    (comp (ref "R27")
      (value "2.2k")
      (footprint "eagle-import:R0603")
      (libsource (lib "eagle-import") (part "R-EU_R0603"))
    )
    (comp (ref "R28")
      (value "22k")
      (footprint "eagle-import:R0603")
      (libsource (lib "eagle-import") (part "R-EU_R0603"))
    )
    (comp (ref "R29")
      (value "3.6k")
      (footprint "eagle-import:R0603")
      (libsource (lib "eagle-import") (part "R-EU_R0603"))
    )
    (comp (ref "R30")
      (value "680")
      (footprint "eagle-import:R0603")
      (libsource (lib "eagle-import") (part "R-EU_R0603"))
    )
    (comp (ref "R31")
      (value "2.2k")
      (footprint "eagle-import:R0603")
      (libsource (lib "eagle-import") (part "R-EU_R0603"))
    )
    (comp (ref "R32")
      (value "2.2k")
      (footprint "eagle-import:R0603")
      (libsource (lib "eagle-import") (part "R-EU_R0603"))
    )
    (comp (ref "R33")
      (value "22k")
      (footprint "eagle-import:R0603")
      (libsource (lib "eagle-import") (part "R-EU_R0603"))
    )
    (comp (ref "R34")
      (value "3.6k")
      (footprint "eagle-import:R0603")
      (libsource (lib "eagle-import") (part "R-EU_R0603"))
    )
    (comp (ref "R35")
      (value "680")
      (footprint "eagle-import:R0603")
      (libsource (lib "eagle-import") (part "R-EU_R0603"))
    )
    (comp (ref "R36")
      (value "2.2k")
      (footprint "eagle-import:R0603")
      (libsource (lib "eagle-import") (part "R-EU_R0603"))
    )
    (comp (ref "R37")
      (value "2.2k")
      (footprint "eagle-import:R0603")
      (libsource (lib "eagle-import") (part "R-EU_R0603"))
    )
    (comp (ref "R38")
      (value "22k")
      (footprint "eagle-import:R0603")
      (libsource (lib "eagle-import") (part "R-EU_R0603"))
    )
    (comp (ref "R39")
      (value "3.6k")
      (footprint "eagle-import:R0603")
      (libsource (lib "eagle-import") (part "R-EU_R0603"))
    )
    (comp (ref "R40")
      (value "680")
      (footprint "eagle-import:R0603")
      (libsource (lib "eagle-import") (part "R-EU_R0603"))
    )
    (comp (ref "R41")
      (value "2.2k")
      (footprint "eagle-import:R0603")
      (libsource (lib "eagle-import") (part "R-EU_R0603"))
    )
    (comp (ref "R42")
      (value "2.2k")
      (footprint "eagle-import:R0603")
      (libsource (lib "eagle-import") (part "R-EU_R0603"))
    )
    (comp (ref "R43")
      (value "22k")
      (footprint "eagle-import:R0603")
      (libsource (lib "eagle-import") (part "R-EU_R0603"))
    )
    (comp (ref "R44")
      (value "3.6k")
      (footprint "eagle-import:R0603")
      (libsource (lib "eagle-import") (part "R-EU_R0603"))
    )
    (comp (ref "R45")
      (value "680")
      (footprint "eagle-import:R0603")
      (libsource (lib "eagle-import") (part "R-EU_R0603"))
    )
    (comp (ref "S1")
      (value "PTS647")
      (footprint "eagle-import:PTS647-TACTSWITCH")
      (libsource (lib "eagle-import") (part "PTS647"))
    )
    (comp (ref "S2")
      (value "PTS647")
      (footprint "eagle-import:PTS647-TACTSWITCH")
      (libsource (lib "eagle-import") (part "PTS647"))
    )
    (comp (ref "S3")
      (value "PTS647")
      (footprint "eagle-import:PTS647-TACTSWITCH")
      (libsource (lib "eagle-import") (part "PTS647"))
    )
    (comp (ref "S4")
      (value "PTS647")
      (footprint "eagle-import:PTS647-TACTSWITCH")
      (libsource (lib "eagle-import") (part "PTS647"))
    )
    (comp (ref "S5")
      (value "PTS647")
      (footprint "eagle-import:PTS647-TACTSWITCH")
      (libsource (lib "eagle-import") (part "PTS647"))
    )
    (comp (ref "S6")
      (value "PTS647")
      (footprint "eagle-import:PTS647-TACTSWITCH")
      (libsource (lib "eagle-import") (part "PTS647"))
    )
    (comp (ref "S7")
      (value "PTS647")
      (footprint "eagle-import:PTS647-TACTSWITCH")
      (libsource (lib "eagle-import") (part "PTS647"))
    )
    (comp (ref "S8")
      (value "PTS647")
      (footprint "eagle-import:PTS647-TACTSWITCH")
      (libsource (lib "eagle-import") (part "PTS647"))
    )
    (comp (ref "S9")
      (value "PTS647")
      (footprint "eagle-import:PTS647-TACTSWITCH")
      (libsource (lib "eagle-import") (part "PTS647"))
    )
  )
  (nets
    (net (code "1") (name "ARD-5V") (class "Default")
      (node (ref "B1") (pin "5V") (pinfunction "5V_5V") (pintype "bidirectional"))
      (node (ref "JP1") (pin "3") (pinfunction "3_3") (pintype "passive"))
    )
    (net (code "2") (name "BAT") (class "Default")
      (node (ref "C22") (pin "1") (pinfunction "+_1") (pintype "passive"))
      (node (ref "JP1") (pin "1") (pinfunction "1_1") (pintype "passive"))
      (node (ref "SL2") (pin "1") (pinfunction "1_1") (pintype "passive"))
    )
    (net (code "3") (name "COL1-1") (class "Default")
      (node (ref "MULT1") (pin "4") (pinfunction "D0_4") (pintype "input"))
      (node (ref "S1") (pin "1") (pinfunction "1_1") (pintype "passive"))
      (node (ref "S1") (pin "2") (pinfunction "1_2") (pintype "passive"))
      (node (ref "S4") (pin "1") (pinfunction "1_1") (pintype "passive"))
      (node (ref "S4") (pin "2") (pinfunction "1_2") (pintype "passive"))
      (node (ref "S7") (pin "1") (pinfunction "1_1") (pintype "passive"))
      (node (ref "S7") (pin "2") (pinfunction "1_2") (pintype "passive"))
    )
    (net (code "4") (name "COL1-2") (class "Default")
      (node (ref "MULT1") (pin "15") (pinfunction "D4_15") (pintype "input"))
      (node (ref "S10") (pin "1") (pinfunction "1_1") (pintype "passive"))
      (node (ref "S10") (pin "2") (pinfunction "1_2") (pintype "passive"))
      (node (ref "S13") (pin "1") (pinfunction "1_1") (pintype "passive"))
      (node (ref "S13") (pin "2") (pinfunction "1_2") (pintype "passive"))
      (node (ref "S16") (pin "1") (pinfunction "1_1") (pintype "passive"))
      (node (ref "S16") (pin "2") (pinfunction "1_2") (pintype "passive"))
    )
    (net (code "5") (name "COL2-1") (class "Default")
      (node (ref "MULT1") (pin "3") (pinfunction "D1_3") (pintype "input"))
      (node (ref "S2") (pin "1") (pinfunction "1_1") (pintype "passive"))
      (node (ref "S2") (pin "2") (pinfunction "1_2") (pintype "passive"))
      (node (ref "S5") (pin "1") (pinfunction "1_1") (pintype "passive"))
      (node (ref "S5") (pin "2") (pinfunction "1_2") (pintype "passive"))
      (node (ref "S8") (pin "1") (pinfunction "1_1") (pintype "passive"))
      (node (ref "S8") (pin "2") (pinfunction "1_2") (pintype "passive"))
    )
    (net (code "6") (name "COL2-2") (class "Default")
      (node (ref "MULT1") (pin "14") (pinfunction "D5_14") (pintype "input"))
      (node (ref "S11") (pin "1") (pinfunction "1_1") (pintype "passive"))
      (node (ref "S11") (pin "2") (pinfunction "1_2") (pintype "passive"))
      (node (ref "S14") (pin "1") (pinfunction "1_1") (pintype "passive"))
      (node (ref "S14") (pin "2") (pinfunction "1_2") (pintype "passive"))
      (node (ref "S17") (pin "1") (pinfunction "1_1") (pintype "passive"))
      (node (ref "S17") (pin "2") (pinfunction "1_2") (pintype "passive"))
    )
    (net (code "7") (name "COL3-1") (class "Default")
      (node (ref "MULT1") (pin "2") (pinfunction "D2_2") (pintype "input"))
      (node (ref "S3") (pin "1") (pinfunction "1_1") (pintype "passive"))
      (node (ref "S3") (pin "2") (pinfunction "1_2") (pintype "passive"))
      (node (ref "S6") (pin "1") (pinfunction "1_1") (pintype "passive"))
      (node (ref "S6") (pin "2") (pinfunction "1_2") (pintype "passive"))
      (node (ref "S9") (pin "1") (pinfunction "1_1") (pintype "passive"))
      (node (ref "S9") (pin "2") (pinfunction "1_2") (pintype "passive"))
    )
    (net (code "8") (name "COL3-2") (class "Default")
      (node (ref "MULT1") (pin "13") (pinfunction "D6_13") (pintype "input"))
      (node (ref "S12") (pin "1") (pinfunction "1_1") (pintype "passive"))
      (node (ref "S12") (pin "2") (pinfunction "1_2") (pintype "passive"))
      (node (ref "S15") (pin "1") (pinfunction "1_1") (pintype "passive"))
      (node (ref "S15") (pin "2") (pinfunction "1_2") (pintype "passive"))
      (node (ref "S18") (pin "1") (pinfunction "1_1") (pintype "passive"))
      (node (ref "S18") (pin "2") (pinfunction "1_2") (pintype "passive"))
    )
    (net (code "9") (name "COLS") (class "Default")
      (node (ref "B1") (pin "D6") (pinfunction "*D6_D6") (pintype "bidirectional"))
      (node (ref "MULT1") (pin "5") (pinfunction "Y_5") (pintype "output"))
    )
    (net (code "10") (name "GND") (class "Default")
      (node (ref "B1") (pin "GND@0") (pinfunction "GND_GND@0") (pintype "bidirectional"))
      (node (ref "B1") (pin "GND@1") (pinfunction "GND_GND@1") (pintype "bidirectional"))
      (node (ref "B1") (pin "GND@2") (pinfunction "GND_GND@2") (pintype "bidirectional"))
      (node (ref "C1") (pin "2") (pinfunction "-_2") (pintype "passive"))
      (node (ref "C10") (pin "2") (pinfunction "-_2") (pintype "passive"))
      (node (ref "C11") (pin "2") (pinfunction "-_2") (pintype "passive"))
      (node (ref "C12") (pin "2") (pinfunction "-_2") (pintype "passive"))
      (node (ref "C13") (pin "2") (pinfunction "-_2") (pintype "passive"))
      (node (ref "C14") (pin "2") (pinfunction "-_2") (pintype "passive"))
      (node (ref "C15") (pin "2") (pinfunction "-_2") (pintype "passive"))
      (node (ref "C16") (pin "2") (pinfunction "-_2") (pintype "passive"))
      (node (ref "C17") (pin "2") (pinfunction "-_2") (pintype "passive"))
      (node (ref "C18") (pin "2") (pinfunction "-_2") (pintype "passive"))
      (node (ref "C19") (pin "2") (pinfunction "2_2") (pintype "passive"))
      (node (ref "C2") (pin "2") (pinfunction "-_2") (pintype "passive"))
      (node (ref "C20") (pin "1") (pinfunction "1_1") (pintype "passive"))
      (node (ref "C21") (pin "1") (pinfunction "1_1") (pintype "passive"))
      (node (ref "C22") (pin "2") (pinfunction "-_2") (pintype "passive"))
      (node (ref "C3") (pin "2") (pinfunction "-_2") (pintype "passive"))
      (node (ref "C4") (pin "2") (pinfunction "-_2") (pintype "passive"))
      (node (ref "C5") (pin "2") (pinfunction "-_2") (pintype "passive"))
      (node (ref "C6") (pin "2") (pinfunction "-_2") (pintype "passive"))
      (node (ref "C7") (pin "2") (pinfunction "-_2") (pintype "passive"))
      (node (ref "C8") (pin "2") (pinfunction "-_2") (pintype "passive"))
      (node (ref "C9") (pin "2") (pinfunction "-_2") (pintype "passive"))
      (node (ref "DRIVER1") (pin "4") (pinfunction "GND1_4") (pintype "power_in"))
      (node (ref "DRIVER1") (pin "9") (pinfunction "GND2_9") (pintype "power_in"))
      (node (ref "MULT1") (pin "1") (pinfunction "D3_1") (pintype "input"))
      (node (ref "MULT1") (pin "12") (pinfunction "D7_12") (pintype "input"))
      (node (ref "MULT1") (pin "7") (pinfunction "NG_7") (pintype "input"))
      (node (ref "MULT1") (pin "8") (pinfunction "GND_8") (pintype "power_in"))
      (node (ref "MUX/DEMUX1") (pin "12") (pinfunction "3_12") (pintype "input"))
      (node (ref "MUX/DEMUX1") (pin "4") (pinfunction "7_4") (pintype "input"))
      (node (ref "MUX/DEMUX1") (pin "6") (pinfunction "INH_6") (pintype "output"))
      (node (ref "MUX/DEMUX1") (pin "7") (pinfunction "VEE_7") (pintype "input"))
      (node (ref "MUX/DEMUX1") (pin "8") (pinfunction "VSS_8") (pintype "power_in"))
      (node (ref "NPN1") (pin "2") (pinfunction "E_2") (pintype "passive"))
      (node (ref "NPN10") (pin "2") (pinfunction "E_2") (pintype "passive"))
      (node (ref "NPN11") (pin "2") (pinfunction "E_2") (pintype "passive"))
      (node (ref "NPN12") (pin "2") (pinfunction "E_2") (pintype "passive"))
      (node (ref "NPN13") (pin "2") (pinfunction "E_2") (pintype "passive"))
      (node (ref "NPN14") (pin "2") (pinfunction "E_2") (pintype "passive"))
      (node (ref "NPN15") (pin "2") (pinfunction "E_2") (pintype "passive"))
      (node (ref "NPN16") (pin "2") (pinfunction "E_2") (pintype "passive"))
      (node (ref "NPN17") (pin "2") (pinfunction "E_2") (pintype "passive"))
      (node (ref "NPN18") (pin "2") (pinfunction "E_2") (pintype "passive"))
      (node (ref "NPN2") (pin "2") (pinfunction "E_2") (pintype "passive"))
      (node (ref "NPN3") (pin "2") (pinfunction "E_2") (pintype "passive"))
      (node (ref "NPN4") (pin "2") (pinfunction "E_2") (pintype "passive"))
      (node (ref "NPN5") (pin "2") (pinfunction "E_2") (pintype "passive"))
      (node (ref "NPN6") (pin "2") (pinfunction "E_2") (pintype "passive"))
      (node (ref "NPN7") (pin "2") (pinfunction "E_2") (pintype "passive"))
      (node (ref "NPN8") (pin "2") (pinfunction "E_2") (pintype "passive"))
      (node (ref "NPN9") (pin "2") (pinfunction "E_2") (pintype "passive"))
      (node (ref "R1") (pin "1") (pinfunction "1_1") (pintype "passive"))
      (node (ref "R11") (pin "1") (pinfunction "1_1") (pintype "passive"))
      (node (ref "R13") (pin "2") (pinfunction "2_2") (pintype "passive"))
      (node (ref "R16") (pin "1") (pinfunction "1_1") (pintype "passive"))
      (node (ref "R18") (pin "2") (pinfunction "2_2") (pintype "passive"))
      (node (ref "R21") (pin "1") (pinfunction "1_1") (pintype "passive"))
      (node (ref "R23") (pin "2") (pinfunction "2_2") (pintype "passive"))
      (node (ref "R26") (pin "1") (pinfunction "1_1") (pintype "passive"))
      (node (ref "R28") (pin "2") (pinfunction "2_2") (pintype "passive"))
      (node (ref "R3") (pin "2") (pinfunction "2_2") (pintype "passive"))
      (node (ref "R31") (pin "1") (pinfunction "1_1") (pintype "passive"))
      (node (ref "R33") (pin "2") (pinfunction "2_2") (pintype "passive"))
      (node (ref "R36") (pin "1") (pinfunction "1_1") (pintype "passive"))
      (node (ref "R38") (pin "2") (pinfunction "2_2") (pintype "passive"))
      (node (ref "R41") (pin "1") (pinfunction "1_1") (pintype "passive"))
      (node (ref "R43") (pin "2") (pinfunction "2_2") (pintype "passive"))
      (node (ref "R46") (pin "1") (pinfunction "1_1") (pintype "passive"))
      (node (ref "R48") (pin "2") (pinfunction "2_2") (pintype "passive"))
      (node (ref "R51") (pin "1") (pinfunction "1_1") (pintype "passive"))
      (node (ref "R53") (pin "2") (pinfunction "2_2") (pintype "passive"))
      (node (ref "R56") (pin "1") (pinfunction "1_1") (pintype "passive"))
      (node (ref "R58") (pin "2") (pinfunction "2_2") (pintype "passive"))
      (node (ref "R6") (pin "1") (pinfunction "1_1") (pintype "passive"))
      (node (ref "R61") (pin "1") (pinfunction "1_1") (pintype "passive"))
      (node (ref "R63") (pin "2") (pinfunction "2_2") (pintype "passive"))
      (node (ref "R66") (pin "1") (pinfunction "1_1") (pintype "passive"))
      (node (ref "R68") (pin "2") (pinfunction "2_2") (pintype "passive"))
      (node (ref "R71") (pin "1") (pinfunction "1_1") (pintype "passive"))
      (node (ref "R73") (pin "2") (pinfunction "2_2") (pintype "passive"))
      (node (ref "R76") (pin "1") (pinfunction "1_1") (pintype "passive"))
      (node (ref "R78") (pin "2") (pinfunction "2_2") (pintype "passive"))
      (node (ref "R8") (pin "2") (pinfunction "2_2") (pintype "passive"))
      (node (ref "R81") (pin "1") (pinfunction "1_1") (pintype "passive"))
      (node (ref "R83") (pin "2") (pinfunction "2_2") (pintype "passive"))
      (node (ref "R86") (pin "1") (pinfunction "1_1") (pintype "passive"))
      (node (ref "R88") (pin "2") (pinfunction "2_2") (pintype "passive"))
      (node (ref "R92") (pin "1") (pinfunction "1_1") (pintype "passive"))
      (node (ref "SL2") (pin "2") (pinfunction "2_2") (pintype "passive"))
    )
    (net (code "11") (name "LOAD") (class "Default")
      (node (ref "B1") (pin "A5") (pinfunction "A5_A5") (pintype "bidirectional"))
      (node (ref "DRIVER1") (pin "12") (pinfunction "LOAD_12") (pintype "bidirectional"))
    )
    (net (code "12") (name "MOSI") (class "Default")
      (node (ref "B1") (pin "D12") (pinfunction "D12_D12") (pintype "bidirectional"))
      (node (ref "DRIVER1") (pin "1") (pinfunction "DIN_1") (pintype "bidirectional"))
    )
    (net (code "13") (name "Net-(C1-+)") (class "Default")
      (node (ref "C1") (pin "1") (pinfunction "+_1") (pintype "passive"))
      (node (ref "R2") (pin "1") (pinfunction "1_1") (pintype "passive"))
      (node (ref "R3") (pin "1") (pinfunction "1_1") (pintype "passive"))
      (node (ref "R4") (pin "1") (pinfunction "1_1") (pintype "passive"))
    )
    (net (code "14") (name "Net-(C2-+)") (class "Default")
      (node (ref "C2") (pin "1") (pinfunction "+_1") (pintype "passive"))
      (node (ref "R7") (pin "1") (pinfunction "1_1") (pintype "passive"))
      (node (ref "R8") (pin "1") (pinfunction "1_1") (pintype "passive"))
      (node (ref "R9") (pin "1") (pinfunction "1_1") (pintype "passive"))
    )
    (net (code "15") (name "Net-(C3-+)") (class "Default")
      (node (ref "C3") (pin "1") (pinfunction "+_1") (pintype "passive"))
      (node (ref "R12") (pin "1") (pinfunction "1_1") (pintype "passive"))
      (node (ref "R13") (pin "1") (pinfunction "1_1") (pintype "passive"))
      (node (ref "R14") (pin "1") (pinfunction "1_1") (pintype "passive"))
    )
    (net (code "16") (name "Net-(C4-+)") (class "Default")
      (node (ref "C4") (pin "1") (pinfunction "+_1") (pintype "passive"))
      (node (ref "R17") (pin "1") (pinfunction "1_1") (pintype "passive"))
      (node (ref "R18") (pin "1") (pinfunction "1_1") (pintype "passive"))
      (node (ref "R19") (pin "1") (pinfunction "1_1") (pintype "passive"))
    )
    (net (code "17") (name "Net-(C5-+)") (class "Default")
      (node (ref "C5") (pin "1") (pinfunction "+_1") (pintype "passive"))
      (node (ref "R22") (pin "1") (pinfunction "1_1") (pintype "passive"))
      (node (ref "R23") (pin "1") (pinfunction "1_1") (pintype "passive"))
      (node (ref "R24") (pin "1") (pinfunction "1_1") (pintype "passive"))
    )
    (net (code "18") (name "Net-(C6-+)") (class "Default")
      (node (ref "C6") (pin "1") (pinfunction "+_1") (pintype "passive"))
      (node (ref "R27") (pin "1") (pinfunction "1_1") (pintype "passive"))
      (node (ref "R28") (pin "1") (pinfunction "1_1") (pintype "passive"))
      (node (ref "R29") (pin "1") (pinfunction "1_1") (pintype "passive"))
    )
    (net (code "19") (name "Net-(C7-+)") (class "Default")
      (node (ref "C7") (pin "1") (pinfunction "+_1") (pintype "passive"))
      (node (ref "R32") (pin "1") (pinfunction "1_1") (pintype "passive"))
      (node (ref "R33") (pin "1") (pinfunction "1_1") (pintype "passive"))
      (node (ref "R34") (pin "1") (pinfunction "1_1") (pintype "passive"))
    )
    (net (code "20") (name "Net-(C8-+)") (class "Default")
      (node (ref "C8") (pin "1") (pinfunction "+_1") (pintype "passive"))
      (node (ref "R37") (pin "1") (pinfunction "1_1") (pintype "passive"))
      (node (ref "R38") (pin "1") (pinfunction "1_1") (pintype "passive"))
      (node (ref "R39") (pin "1") (pinfunction "1_1") (pintype "passive"))
    )
    (net (code "21") (name "Net-(C9-+)") (class "Default")
      (node (ref "C9") (pin "1") (pinfunction "+_1") (pintype "passive"))
      (node (ref "R42") (pin "1") (pinfunction "1_1") (pintype "passive"))
      (node (ref "R43") (pin "1") (pinfunction "1_1") (pintype "passive"))
      (node (ref "R44") (pin "1") (pinfunction "1_1") (pintype "passive"))
    )
    (net (code "22") (name "Net-(C10-+)") (class "Default")
      (node (ref "C10") (pin "1") (pinfunction "+_1") (pintype "passive"))
      (node (ref "R47") (pin "1") (pinfunction "1_1") (pintype "passive"))
      (node (ref "R48") (pin "1") (pinfunction "1_1") (pintype "passive"))
      (node (ref "R49") (pin "1") (pinfunction "1_1") (pintype "passive"))
    )
    (net (code "23") (name "Net-(C11-+)") (class "Default")
      (node (ref "C11") (pin "1") (pinfunction "+_1") (pintype "passive"))
      (node (ref "R52") (pin "1") (pinfunction "1_1") (pintype "passive"))
      (node (ref "R53") (pin "1") (pinfunction "1_1") (pintype "passive"))
      (node (ref "R54") (pin "1") (pinfunction "1_1") (pintype "passive"))
    )
    (net (code "24") (name "Net-(C12-+)") (class "Default")
      (node (ref "C12") (pin "1") (pinfunction "+_1") (pintype "passive"))
      (node (ref "R57") (pin "1") (pinfunction "1_1") (pintype "passive"))
      (node (ref "R58") (pin "1") (pinfunction "1_1") (pintype "passive"))
      (node (ref "R59") (pin "1") (pinfunction "1_1") (pintype "passive"))
    )
    (net (code "25") (name "Net-(C13-+)") (class "Default")
      (node (ref "C13") (pin "1") (pinfunction "+_1") (pintype "passive"))
      (node (ref "R62") (pin "1") (pinfunction "1_1") (pintype "passive"))
      (node (ref "R63") (pin "1") (pinfunction "1_1") (pintype "passive"))
      (node (ref "R64") (pin "1") (pinfunction "1_1") (pintype "passive"))
    )
    (net (code "26") (name "Net-(C14-+)") (class "Default")
      (node (ref "C14") (pin "1") (pinfunction "+_1") (pintype "passive"))
      (node (ref "R67") (pin "1") (pinfunction "1_1") (pintype "passive"))
      (node (ref "R68") (pin "1") (pinfunction "1_1") (pintype "passive"))
      (node (ref "R69") (pin "1") (pinfunction "1_1") (pintype "passive"))
    )
    (net (code "27") (name "Net-(C15-+)") (class "Default")
      (node (ref "C15") (pin "1") (pinfunction "+_1") (pintype "passive"))
      (node (ref "R72") (pin "1") (pinfunction "1_1") (pintype "passive"))
      (node (ref "R73") (pin "1") (pinfunction "1_1") (pintype "passive"))
      (node (ref "R74") (pin "1") (pinfunction "1_1") (pintype "passive"))
    )
    (net (code "28") (name "Net-(C16-+)") (class "Default")
      (node (ref "C16") (pin "1") (pinfunction "+_1") (pintype "passive"))
      (node (ref "R77") (pin "1") (pinfunction "1_1") (pintype "passive"))
      (node (ref "R78") (pin "1") (pinfunction "1_1") (pintype "passive"))
      (node (ref "R79") (pin "1") (pinfunction "1_1") (pintype "passive"))
    )
    (net (code "29") (name "Net-(C17-+)") (class "Default")
      (node (ref "C17") (pin "1") (pinfunction "+_1") (pintype "passive"))
      (node (ref "R82") (pin "1") (pinfunction "1_1") (pintype "passive"))
      (node (ref "R83") (pin "1") (pinfunction "1_1") (pintype "passive"))
      (node (ref "R84") (pin "1") (pinfunction "1_1") (pintype "passive"))
    )
    (net (code "30") (name "Net-(C18-+)") (class "Default")
      (node (ref "C18") (pin "1") (pinfunction "+_1") (pintype "passive"))
      (node (ref "R87") (pin "1") (pinfunction "1_1") (pintype "passive"))
      (node (ref "R88") (pin "1") (pinfunction "1_1") (pintype "passive"))
      (node (ref "R89") (pin "1") (pinfunction "1_1") (pintype "passive"))
    )
    (net (code "31") (name "Net-(D1-A)") (class "Default")
      (node (ref "D1") (pin "2") (pinfunction "A_2") (pintype "passive"))
      (node (ref "R1") (pin "2") (pinfunction "2_2") (pintype "passive"))
      (node (ref "R2") (pin "2") (pinfunction "2_2") (pintype "passive"))
      (node (ref "S1") (pin "3") (pinfunction "2_3") (pintype "passive"))
      (node (ref "S1") (pin "4") (pinfunction "2_4") (pintype "passive"))
    )
    (net (code "32") (name "Net-(D2-A)") (class "Default")
      (node (ref "D2") (pin "2") (pinfunction "A_2") (pintype "passive"))
      (node (ref "R6") (pin "2") (pinfunction "2_2") (pintype "passive"))
      (node (ref "R7") (pin "2") (pinfunction "2_2") (pintype "passive"))
      (node (ref "S2") (pin "3") (pinfunction "2_3") (pintype "passive"))
      (node (ref "S2") (pin "4") (pinfunction "2_4") (pintype "passive"))
    )
    (net (code "33") (name "Net-(D3-A)") (class "Default")
      (node (ref "D3") (pin "2") (pinfunction "A_2") (pintype "passive"))
      (node (ref "R11") (pin "2") (pinfunction "2_2") (pintype "passive"))
      (node (ref "R12") (pin "2") (pinfunction "2_2") (pintype "passive"))
      (node (ref "S3") (pin "3") (pinfunction "2_3") (pintype "passive"))
      (node (ref "S3") (pin "4") (pinfunction "2_4") (pintype "passive"))
    )
    (net (code "34") (name "Net-(D4-A)") (class "Default")
      (node (ref "D4") (pin "2") (pinfunction "A_2") (pintype "passive"))
      (node (ref "R16") (pin "2") (pinfunction "2_2") (pintype "passive"))
      (node (ref "R17") (pin "2") (pinfunction "2_2") (pintype "passive"))
      (node (ref "S4") (pin "3") (pinfunction "2_3") (pintype "passive"))
      (node (ref "S4") (pin "4") (pinfunction "2_4") (pintype "passive"))
    )
    (net (code "35") (name "Net-(D5-A)") (class "Default")
      (node (ref "D5") (pin "2") (pinfunction "A_2") (pintype "passive"))
      (node (ref "R21") (pin "2") (pinfunction "2_2") (pintype "passive"))
      (node (ref "R22") (pin "2") (pinfunction "2_2") (pintype "passive"))
      (node (ref "S5") (pin "3") (pinfunction "2_3") (pintype "passive"))
      (node (ref "S5") (pin "4") (pinfunction "2_4") (pintype "passive"))
    )
    (net (code "36") (name "Net-(D6-A)") (class "Default")
      (node (ref "D6") (pin "2") (pinfunction "A_2") (pintype "passive"))
      (node (ref "R26") (pin "2") (pinfunction "2_2") (pintype "passive"))
      (node (ref "R27") (pin "2") (pinfunction "2_2") (pintype "passive"))
      (node (ref "S6") (pin "3") (pinfunction "2_3") (pintype "passive"))
      (node (ref "S6") (pin "4") (pinfunction "2_4") (pintype "passive"))
    )
    (net (code "37") (name "Net-(D7-A)") (class "Default")
      (node (ref "D7") (pin "2") (pinfunction "A_2") (pintype "passive"))
      (node (ref "R31") (pin "2") (pinfunction "2_2") (pintype "passive"))
      (node (ref "R32") (pin "2") (pinfunction "2_2") (pintype "passive"))
      (node (ref "S7") (pin "3") (pinfunction "2_3") (pintype "passive"))
      (node (ref "S7") (pin "4") (pinfunction "2_4") (pintype "passive"))
    )
    (net (code "38") (name "Net-(D8-A)") (class "Default")
      (node (ref "D8") (pin "2") (pinfunction "A_2") (pintype "passive"))
      (node (ref "R36") (pin "2") (pinfunction "2_2") (pintype "passive"))
      (node (ref "R37") (pin "2") (pinfunction "2_2") (pintype "passive"))
      (node (ref "S8") (pin "3") (pinfunction "2_3") (pintype "passive"))
      (node (ref "S8") (pin "4") (pinfunction "2_4") (pintype "passive"))
    )
    (net (code "39") (name "Net-(D9-A)") (class "Default")
      (node (ref "D9") (pin "2") (pinfunction "A_2") (pintype "passive"))
      (node (ref "R41") (pin "2") (pinfunction "2_2") (pintype "passive"))
      (node (ref "R42") (pin "2") (pinfunction "2_2") (pintype "passive"))
      (node (ref "S9") (pin "3") (pinfunction "2_3") (pintype "passive"))
      (node (ref "S9") (pin "4") (pinfunction "2_4") (pintype "passive"))
    )
    (net (code "40") (name "Net-(D10-A)") (class "Default")
      (node (ref "D10") (pin "2") (pinfunction "A_2") (pintype "passive"))
      (node (ref "R46") (pin "2") (pinfunction "2_2") (pintype "passive"))
      (node (ref "R47") (pin "2") (pinfunction "2_2") (pintype "passive"))
      (node (ref "S10") (pin "3") (pinfunction "2_3") (pintype "passive"))
      (node (ref "S10") (pin "4") (pinfunction "2_4") (pintype "passive"))
    )
    (net (code "41") (name "Net-(D11-A)") (class "Default")
      (node (ref "D11") (pin "2") (pinfunction "A_2") (pintype "passive"))
      (node (ref "R51") (pin "2") (pinfunction "2_2") (pintype "passive"))
      (node (ref "R52") (pin "2") (pinfunction "2_2") (pintype "passive"))
      (node (ref "S11") (pin "3") (pinfunction "2_3") (pintype "passive"))
      (node (ref "S11") (pin "4") (pinfunction "2_4") (pintype "passive"))
    )
    (net (code "42") (name "Net-(D12-A)") (class "Default")
      (node (ref "D12") (pin "2") (pinfunction "A_2") (pintype "passive"))
      (node (ref "R56") (pin "2") (pinfunction "2_2") (pintype "passive"))
      (node (ref "R57") (pin "2") (pinfunction "2_2") (pintype "passive"))
      (node (ref "S12") (pin "3") (pinfunction "2_3") (pintype "passive"))
      (node (ref "S12") (pin "4") (pinfunction "2_4") (pintype "passive"))
    )
    (net (code "43") (name "Net-(D13-A)") (class "Default")
      (node (ref "D13") (pin "2") (pinfunction "A_2") (pintype "passive"))
      (node (ref "R61") (pin "2") (pinfunction "2_2") (pintype "passive"))
      (node (ref "R62") (pin "2") (pinfunction "2_2") (pintype "passive"))
      (node (ref "S13") (pin "3") (pinfunction "2_3") (pintype "passive"))
      (node (ref "S13") (pin "4") (pinfunction "2_4") (pintype "passive"))
    )
    (net (code "44") (name "Net-(D14-A)") (class "Default")
      (node (ref "D14") (pin "2") (pinfunction "A_2") (pintype "passive"))
      (node (ref "R66") (pin "2") (pinfunction "2_2") (pintype "passive"))
      (node (ref "R67") (pin "2") (pinfunction "2_2") (pintype "passive"))
      (node (ref "S14") (pin "3") (pinfunction "2_3") (pintype "passive"))
      (node (ref "S14") (pin "4") (pinfunction "2_4") (pintype "passive"))
    )
    (net (code "45") (name "Net-(D15-A)") (class "Default")
      (node (ref "D15") (pin "2") (pinfunction "A_2") (pintype "passive"))
      (node (ref "R71") (pin "2") (pinfunction "2_2") (pintype "passive"))
      (node (ref "R72") (pin "2") (pinfunction "2_2") (pintype "passive"))
      (node (ref "S15") (pin "3") (pinfunction "2_3") (pintype "passive"))
      (node (ref "S15") (pin "4") (pinfunction "2_4") (pintype "passive"))
    )
    (net (code "46") (name "Net-(D16-A)") (class "Default")
      (node (ref "D16") (pin "2") (pinfunction "A_2") (pintype "passive"))
      (node (ref "R76") (pin "2") (pinfunction "2_2") (pintype "passive"))
      (node (ref "R77") (pin "2") (pinfunction "2_2") (pintype "passive"))
      (node (ref "S16") (pin "3") (pinfunction "2_3") (pintype "passive"))
      (node (ref "S16") (pin "4") (pinfunction "2_4") (pintype "passive"))
    )
    (net (code "47") (name "Net-(D17-A)") (class "Default")
      (node (ref "D17") (pin "2") (pinfunction "A_2") (pintype "passive"))
      (node (ref "R81") (pin "2") (pinfunction "2_2") (pintype "passive"))
      (node (ref "R82") (pin "2") (pinfunction "2_2") (pintype "passive"))
      (node (ref "S17") (pin "3") (pinfunction "2_3") (pintype "passive"))
      (node (ref "S17") (pin "4") (pinfunction "2_4") (pintype "passive"))
    )
    (net (code "48") (name "Net-(D18-A)") (class "Default")
      (node (ref "D18") (pin "2") (pinfunction "A_2") (pintype "passive"))
      (node (ref "R86") (pin "2") (pinfunction "2_2") (pintype "passive"))
      (node (ref "R87") (pin "2") (pinfunction "2_2") (pintype "passive"))
      (node (ref "S18") (pin "3") (pinfunction "2_3") (pintype "passive"))
      (node (ref "S18") (pin "4") (pinfunction "2_4") (pintype "passive"))
    )
    (net (code "49") (name "Net-(DRIVER1-ISET)") (class "Default")
      (node (ref "DRIVER1") (pin "18") (pinfunction "ISET_18") (pintype "power_in"))
      (node (ref "R93") (pin "1") (pinfunction "1_1") (pintype "passive"))
    )
    (net (code "50") (name "Net-(L1-C)") (class "Default")
      (node (ref "L1") (pin "1") (pinfunction "C_1") (pintype "passive"))
      (node (ref "R5") (pin "2") (pinfunction "2_2") (pintype "passive"))
    )
    (net (code "51") (name "Net-(L2-C)") (class "Default")
      (node (ref "L2") (pin "1") (pinfunction "C_1") (pintype "passive"))
      (node (ref "R10") (pin "2") (pinfunction "2_2") (pintype "passive"))
    )
    (net (code "52") (name "Net-(L3-C)") (class "Default")
      (node (ref "L3") (pin "1") (pinfunction "C_1") (pintype "passive"))
      (node (ref "R15") (pin "2") (pinfunction "2_2") (pintype "passive"))
    )
    (net (code "53") (name "Net-(L4-C)") (class "Default")
      (node (ref "L4") (pin "1") (pinfunction "C_1") (pintype "passive"))
      (node (ref "R20") (pin "2") (pinfunction "2_2") (pintype "passive"))
    )
    (net (code "54") (name "Net-(L5-C)") (class "Default")
      (node (ref "L5") (pin "1") (pinfunction "C_1") (pintype "passive"))
      (node (ref "R25") (pin "2") (pinfunction "2_2") (pintype "passive"))
    )
    (net (code "55") (name "Net-(L6-C)") (class "Default")
      (node (ref "L6") (pin "1") (pinfunction "C_1") (pintype "passive"))
      (node (ref "R30") (pin "2") (pinfunction "2_2") (pintype "passive"))
    )
    (net (code "56") (name "Net-(L7-C)") (class "Default")
      (node (ref "L7") (pin "1") (pinfunction "C_1") (pintype "passive"))
      (node (ref "R35") (pin "2") (pinfunction "2_2") (pintype "passive"))
    )
    (net (code "57") (name "Net-(L8-C)") (class "Default")
      (node (ref "L8") (pin "1") (pinfunction "C_1") (pintype "passive"))
      (node (ref "R40") (pin "2") (pinfunction "2_2") (pintype "passive"))
    )
    (net (code "58") (name "Net-(L9-C)") (class "Default")
      (node (ref "L9") (pin "1") (pinfunction "C_1") (pintype "passive"))
      (node (ref "R45") (pin "2") (pinfunction "2_2") (pintype "passive"))
    )
    (net (code "59") (name "Net-(L10-C)") (class "Default")
      (node (ref "L10") (pin "1") (pinfunction "C_1") (pintype "passive"))
      (node (ref "R50") (pin "2") (pinfunction "2_2") (pintype "passive"))
    )
    (net (code "60") (name "Net-(L11-C)") (class "Default")
      (node (ref "L11") (pin "1") (pinfunction "C_1") (pintype "passive"))
      (node (ref "R55") (pin "2") (pinfunction "2_2") (pintype "passive"))
    )
    (net (code "61") (name "Net-(L12-C)") (class "Default")
      (node (ref "L12") (pin "1") (pinfunction "C_1") (pintype "passive"))
      (node (ref "R60") (pin "2") (pinfunction "2_2") (pintype "passive"))
    )
    (net (code "62") (name "Net-(L13-C)") (class "Default")
      (node (ref "L13") (pin "1") (pinfunction "C_1") (pintype "passive"))
      (node (ref "R65") (pin "2") (pinfunction "2_2") (pintype "passive"))
    )
    (net (code "63") (name "Net-(L14-C)") (class "Default")
      (node (ref "L14") (pin "1") (pinfunction "C_1") (pintype "passive"))
      (node (ref "R70") (pin "2") (pinfunction "2_2") (pintype "passive"))
    )
    (net (code "64") (name "Net-(L15-C)") (class "Default")
      (node (ref "L15") (pin "1") (pinfunction "C_1") (pintype "passive"))
      (node (ref "R75") (pin "2") (pinfunction "2_2") (pintype "passive"))
    )
    (net (code "65") (name "Net-(L16-C)") (class "Default")
      (node (ref "L16") (pin "1") (pinfunction "C_1") (pintype "passive"))
      (node (ref "R80") (pin "2") (pinfunction "2_2") (pintype "passive"))
    )
    (net (code "66") (name "Net-(L17-C)") (class "Default")
      (node (ref "L17") (pin "1") (pinfunction "C_1") (pintype "passive"))
      (node (ref "R85") (pin "2") (pinfunction "2_2") (pintype "passive"))
    )
    (net (code "67") (name "Net-(L18-C)") (class "Default")
      (node (ref "L18") (pin "1") (pinfunction "C_1") (pintype "passive"))
      (node (ref "R90") (pin "2") (pinfunction "2_2") (pintype "passive"))
    )
    (net (code "68") (name "Net-(L19-C)") (class "Default")
      (node (ref "L19") (pin "1") (pinfunction "C_1") (pintype "passive"))
      (node (ref "R91") (pin "2") (pinfunction "2_2") (pintype "passive"))
    )
    (net (code "69") (name "Net-(L20-C)") (class "Default")
      (node (ref "L20") (pin "1") (pinfunction "C_1") (pintype "passive"))
      (node (ref "R92") (pin "2") (pinfunction "2_2") (pintype "passive"))
    )
    (net (code "70") (name "Net-(NPN1-B)") (class "Default")
      (node (ref "NPN1") (pin "1") (pinfunction "B_1") (pintype "passive"))
      (node (ref "R4") (pin "2") (pinfunction "2_2") (pintype "passive"))
    )
    (net (code "71") (name "Net-(NPN1-C)") (class "Default")
      (node (ref "NPN1") (pin "3") (pinfunction "C_3") (pintype "passive"))
      (node (ref "R5") (pin "1") (pinfunction "1_1") (pintype "passive"))
    )
    (net (code "72") (name "Net-(NPN2-B)") (class "Default")
      (node (ref "NPN2") (pin "1") (pinfunction "B_1") (pintype "passive"))
      (node (ref "R9") (pin "2") (pinfunction "2_2") (pintype "passive"))
    )
    (net (code "73") (name "Net-(NPN2-C)") (class "Default")
      (node (ref "NPN2") (pin "3") (pinfunction "C_3") (pintype "passive"))
      (node (ref "R10") (pin "1") (pinfunction "1_1") (pintype "passive"))
    )
    (net (code "74") (name "Net-(NPN3-B)") (class "Default")
      (node (ref "NPN3") (pin "1") (pinfunction "B_1") (pintype "passive"))
      (node (ref "R14") (pin "2") (pinfunction "2_2") (pintype "passive"))
    )
    (net (code "75") (name "Net-(NPN3-C)") (class "Default")
      (node (ref "NPN3") (pin "3") (pinfunction "C_3") (pintype "passive"))
      (node (ref "R15") (pin "1") (pinfunction "1_1") (pintype "passive"))
    )
    (net (code "76") (name "Net-(NPN4-B)") (class "Default")
      (node (ref "NPN4") (pin "1") (pinfunction "B_1") (pintype "passive"))
      (node (ref "R19") (pin "2") (pinfunction "2_2") (pintype "passive"))
    )
    (net (code "77") (name "Net-(NPN4-C)") (class "Default")
      (node (ref "NPN4") (pin "3") (pinfunction "C_3") (pintype "passive"))
      (node (ref "R20") (pin "1") (pinfunction "1_1") (pintype "passive"))
    )
    (net (code "78") (name "Net-(NPN5-B)") (class "Default")
      (node (ref "NPN5") (pin "1") (pinfunction "B_1") (pintype "passive"))
      (node (ref "R24") (pin "2") (pinfunction "2_2") (pintype "passive"))
    )
    (net (code "79") (name "Net-(NPN5-C)") (class "Default")
      (node (ref "NPN5") (pin "3") (pinfunction "C_3") (pintype "passive"))
      (node (ref "R25") (pin "1") (pinfunction "1_1") (pintype "passive"))
    )
    (net (code "80") (name "Net-(NPN6-B)") (class "Default")
      (node (ref "NPN6") (pin "1") (pinfunction "B_1") (pintype "passive"))
      (node (ref "R29") (pin "2") (pinfunction "2_2") (pintype "passive"))
    )
    (net (code "81") (name "Net-(NPN6-C)") (class "Default")
      (node (ref "NPN6") (pin "3") (pinfunction "C_3") (pintype "passive"))
      (node (ref "R30") (pin "1") (pinfunction "1_1") (pintype "passive"))
    )
    (net (code "82") (name "Net-(NPN7-B)") (class "Default")
      (node (ref "NPN7") (pin "1") (pinfunction "B_1") (pintype "passive"))
      (node (ref "R34") (pin "2") (pinfunction "2_2") (pintype "passive"))
    )
    (net (code "83") (name "Net-(NPN7-C)") (class "Default")
      (node (ref "NPN7") (pin "3") (pinfunction "C_3") (pintype "passive"))
      (node (ref "R35") (pin "1") (pinfunction "1_1") (pintype "passive"))
    )
    (net (code "84") (name "Net-(NPN8-B)") (class "Default")
      (node (ref "NPN8") (pin "1") (pinfunction "B_1") (pintype "passive"))
      (node (ref "R39") (pin "2") (pinfunction "2_2") (pintype "passive"))
    )
    (net (code "85") (name "Net-(NPN8-C)") (class "Default")
      (node (ref "NPN8") (pin "3") (pinfunction "C_3") (pintype "passive"))
      (node (ref "R40") (pin "1") (pinfunction "1_1") (pintype "passive"))
    )
    (net (code "86") (name "Net-(NPN9-B)") (class "Default")
      (node (ref "NPN9") (pin "1") (pinfunction "B_1") (pintype "passive"))
      (node (ref "R44") (pin "2") (pinfunction "2_2") (pintype "passive"))
    )
    (net (code "87") (name "Net-(NPN9-C)") (class "Default")
      (node (ref "NPN9") (pin "3") (pinfunction "C_3") (pintype "passive"))
      (node (ref "R45") (pin "1") (pinfunction "1_1") (pintype "passive"))
    )
    (net (code "88") (name "Net-(NPN10-B)") (class "Default")
      (node (ref "NPN10") (pin "1") (pinfunction "B_1") (pintype "passive"))
      (node (ref "R49") (pin "2") (pinfunction "2_2") (pintype "passive"))
    )
    (net (code "89") (name "Net-(NPN10-C)") (class "Default")
      (node (ref "NPN10") (pin "3") (pinfunction "C_3") (pintype "passive"))
      (node (ref "R50") (pin "1") (pinfunction "1_1") (pintype "passive"))
    )
    (net (code "90") (name "Net-(NPN11-B)") (class "Default")
      (node (ref "NPN11") (pin "1") (pinfunction "B_1") (pintype "passive"))
      (node (ref "R54") (pin "2") (pinfunction "2_2") (pintype "passive"))
    )
    (net (code "91") (name "Net-(NPN11-C)") (class "Default")
      (node (ref "NPN11") (pin "3") (pinfunction "C_3") (pintype "passive"))
      (node (ref "R55") (pin "1") (pinfunction "1_1") (pintype "passive"))
    )
    (net (code "92") (name "Net-(NPN12-B)") (class "Default")
      (node (ref "NPN12") (pin "1") (pinfunction "B_1") (pintype "passive"))
      (node (ref "R59") (pin "2") (pinfunction "2_2") (pintype "passive"))
    )
    (net (code "93") (name "Net-(NPN12-C)") (class "Default")
      (node (ref "NPN12") (pin "3") (pinfunction "C_3") (pintype "passive"))
      (node (ref "R60") (pin "1") (pinfunction "1_1") (pintype "passive"))
    )
    (net (code "94") (name "Net-(NPN13-B)") (class "Default")
      (node (ref "NPN13") (pin "1") (pinfunction "B_1") (pintype "passive"))
      (node (ref "R64") (pin "2") (pinfunction "2_2") (pintype "passive"))
    )
    (net (code "95") (name "Net-(NPN13-C)") (class "Default")
      (node (ref "NPN13") (pin "3") (pinfunction "C_3") (pintype "passive"))
      (node (ref "R65") (pin "1") (pinfunction "1_1") (pintype "passive"))
    )
    (net (code "96") (name "Net-(NPN14-B)") (class "Default")
      (node (ref "NPN14") (pin "1") (pinfunction "B_1") (pintype "passive"))
      (node (ref "R69") (pin "2") (pinfunction "2_2") (pintype "passive"))
    )
    (net (code "97") (name "Net-(NPN14-C)") (class "Default")
      (node (ref "NPN14") (pin "3") (pinfunction "C_3") (pintype "passive"))
      (node (ref "R70") (pin "1") (pinfunction "1_1") (pintype "passive"))
    )
    (net (code "98") (name "Net-(NPN15-B)") (class "Default")
      (node (ref "NPN15") (pin "1") (pinfunction "B_1") (pintype "passive"))
      (node (ref "R74") (pin "2") (pinfunction "2_2") (pintype "passive"))
    )
    (net (code "99") (name "Net-(NPN15-C)") (class "Default")
      (node (ref "NPN15") (pin "3") (pinfunction "C_3") (pintype "passive"))
      (node (ref "R75") (pin "1") (pinfunction "1_1") (pintype "passive"))
    )
    (net (code "100") (name "Net-(NPN16-B)") (class "Default")
      (node (ref "NPN16") (pin "1") (pinfunction "B_1") (pintype "passive"))
      (node (ref "R79") (pin "2") (pinfunction "2_2") (pintype "passive"))
    )
    (net (code "101") (name "Net-(NPN16-C)") (class "Default")
      (node (ref "NPN16") (pin "3") (pinfunction "C_3") (pintype "passive"))
      (node (ref "R80") (pin "1") (pinfunction "1_1") (pintype "passive"))
    )
    (net (code "102") (name "Net-(NPN17-B)") (class "Default")
      (node (ref "NPN17") (pin "1") (pinfunction "B_1") (pintype "passive"))
      (node (ref "R84") (pin "2") (pinfunction "2_2") (pintype "passive"))
    )
    (net (code "103") (name "Net-(NPN17-C)") (class "Default")
      (node (ref "NPN17") (pin "3") (pinfunction "C_3") (pintype "passive"))
      (node (ref "R85") (pin "1") (pinfunction "1_1") (pintype "passive"))
    )
    (net (code "104") (name "Net-(NPN18-B)") (class "Default")
      (node (ref "NPN18") (pin "1") (pinfunction "B_1") (pintype "passive"))
      (node (ref "R89") (pin "2") (pinfunction "2_2") (pintype "passive"))
    )
    (net (code "105") (name "Net-(NPN18-C)") (class "Default")
      (node (ref "NPN18") (pin "3") (pinfunction "C_3") (pintype "passive"))
      (node (ref "R90") (pin "1") (pinfunction "1_1") (pintype "passive"))
    )
    (net (code "106") (name "OUT-COL1-G") (class "Default")
      (node (ref "BL1") (pin "4") (pinfunction "AG_4") (pintype "passive"))
      (node (ref "BL4") (pin "4") (pinfunction "AG_4") (pintype "passive"))
      (node (ref "BL7") (pin "4") (pinfunction "AG_4") (pintype "passive"))
      (node (ref "DRIVER1") (pin "16") (pinfunction "SEGB_16") (pintype "bidirectional"))
    )
    (net (code "107") (name "OUT-COL1-R") (class "Default")
      (node (ref "BL1") (pin "1") (pinfunction "AR_1") (pintype "passive"))
      (node (ref "BL4") (pin "1") (pinfunction "AR_1") (pintype "passive"))
      (node (ref "BL7") (pin "1") (pinfunction "AR_1") (pintype "passive"))
      (node (ref "DRIVER1") (pin "14") (pinfunction "SEGA_14") (pintype "bidirectional"))
    )
    (net (code "108") (name "OUT-COL2-G") (class "Default")
      (node (ref "BL2") (pin "4") (pinfunction "AG_4") (pintype "passive"))
      (node (ref "BL5") (pin "4") (pinfunction "AG_4") (pintype "passive"))
      (node (ref "BL8") (pin "4") (pinfunction "AG_4") (pintype "passive"))
      (node (ref "DRIVER1") (pin "23") (pinfunction "SEGD_23") (pintype "bidirectional"))
    )
    (net (code "109") (name "OUT-COL2-R") (class "Default")
      (node (ref "BL2") (pin "1") (pinfunction "AR_1") (pintype "passive"))
      (node (ref "BL5") (pin "1") (pinfunction "AR_1") (pintype "passive"))
      (node (ref "BL8") (pin "1") (pinfunction "AR_1") (pintype "passive"))
      (node (ref "DRIVER1") (pin "20") (pinfunction "SEGC_20") (pintype "bidirectional"))
    )
    (net (code "110") (name "OUT-COL3-G") (class "Default")
      (node (ref "BL3") (pin "4") (pinfunction "AG_4") (pintype "passive"))
      (node (ref "BL6") (pin "4") (pinfunction "AG_4") (pintype "passive"))
      (node (ref "BL9") (pin "4") (pinfunction "AG_4") (pintype "passive"))
      (node (ref "DRIVER1") (pin "15") (pinfunction "SEGF_15") (pintype "bidirectional"))
    )
    (net (code "111") (name "OUT-COL3-R") (class "Default")
      (node (ref "BL3") (pin "1") (pinfunction "AR_1") (pintype "passive"))
      (node (ref "BL6") (pin "1") (pinfunction "AR_1") (pintype "passive"))
      (node (ref "BL9") (pin "1") (pinfunction "AR_1") (pintype "passive"))
      (node (ref "DRIVER1") (pin "21") (pinfunction "SEGE_21") (pintype "bidirectional"))
    )
    (net (code "112") (name "OUT-ROW1") (class "Default")
      (node (ref "BL1") (pin "2") (pinfunction "CR_2") (pintype "passive"))
      (node (ref "BL1") (pin "3") (pinfunction "CG_3") (pintype "passive"))
      (node (ref "BL2") (pin "2") (pinfunction "CR_2") (pintype "passive"))
      (node (ref "BL2") (pin "3") (pinfunction "CG_3") (pintype "passive"))
      (node (ref "BL3") (pin "2") (pinfunction "CR_2") (pintype "passive"))
      (node (ref "BL3") (pin "3") (pinfunction "CG_3") (pintype "passive"))
      (node (ref "DRIVER1") (pin "2") (pinfunction "DIG0_2") (pintype "bidirectional"))
    )
    (net (code "113") (name "OUT-ROW2") (class "Default")
      (node (ref "BL4") (pin "2") (pinfunction "CR_2") (pintype "passive"))
      (node (ref "BL4") (pin "3") (pinfunction "CG_3") (pintype "passive"))
      (node (ref "BL5") (pin "2") (pinfunction "CR_2") (pintype "passive"))
      (node (ref "BL5") (pin "3") (pinfunction "CG_3") (pintype "passive"))
      (node (ref "BL6") (pin "2") (pinfunction "CR_2") (pintype "passive"))
      (node (ref "BL6") (pin "3") (pinfunction "CG_3") (pintype "passive"))
      (node (ref "DRIVER1") (pin "6") (pinfunction "DIG2_6") (pintype "bidirectional"))
    )
    (net (code "114") (name "OUT-ROW3") (class "Default")
      (node (ref "BL7") (pin "2") (pinfunction "CR_2") (pintype "passive"))
      (node (ref "BL7") (pin "3") (pinfunction "CG_3") (pintype "passive"))
      (node (ref "BL8") (pin "2") (pinfunction "CR_2") (pintype "passive"))
      (node (ref "BL8") (pin "3") (pinfunction "CG_3") (pintype "passive"))
      (node (ref "BL9") (pin "2") (pinfunction "CR_2") (pintype "passive"))
      (node (ref "BL9") (pin "3") (pinfunction "CG_3") (pintype "passive"))
      (node (ref "DRIVER1") (pin "11") (pinfunction "DIG1_11") (pintype "bidirectional"))
    )
    (net (code "115") (name "ROW1-1") (class "Default")
      (node (ref "D1") (pin "1") (pinfunction "C_1") (pintype "passive"))
      (node (ref "D2") (pin "1") (pinfunction "C_1") (pintype "passive"))
      (node (ref "D3") (pin "1") (pinfunction "C_1") (pintype "passive"))
      (node (ref "MUX/DEMUX1") (pin "13") (pinfunction "0_13") (pintype "input"))
    )
    (net (code "116") (name "ROW1-2") (class "Default")
      (node (ref "D10") (pin "1") (pinfunction "C_1") (pintype "passive"))
      (node (ref "D11") (pin "1") (pinfunction "C_1") (pintype "passive"))
      (node (ref "D12") (pin "1") (pinfunction "C_1") (pintype "passive"))
      (node (ref "MUX/DEMUX1") (pin "1") (pinfunction "4_1") (pintype "input"))
    )
    (net (code "117") (name "ROW2-1") (class "Default")
      (node (ref "D4") (pin "1") (pinfunction "C_1") (pintype "passive"))
      (node (ref "D5") (pin "1") (pinfunction "C_1") (pintype "passive"))
      (node (ref "D6") (pin "1") (pinfunction "C_1") (pintype "passive"))
      (node (ref "MUX/DEMUX1") (pin "14") (pinfunction "1_14") (pintype "input"))
    )
    (net (code "118") (name "ROW2-2") (class "Default")
      (node (ref "D13") (pin "1") (pinfunction "C_1") (pintype "passive"))
      (node (ref "D14") (pin "1") (pinfunction "C_1") (pintype "passive"))
      (node (ref "D15") (pin "1") (pinfunction "C_1") (pintype "passive"))
      (node (ref "MUX/DEMUX1") (pin "5") (pinfunction "5_5") (pintype "output"))
    )
    (net (code "119") (name "ROW3-1") (class "Default")
      (node (ref "D7") (pin "1") (pinfunction "C_1") (pintype "passive"))
      (node (ref "D8") (pin "1") (pinfunction "C_1") (pintype "passive"))
      (node (ref "D9") (pin "1") (pinfunction "C_1") (pintype "passive"))
      (node (ref "MUX/DEMUX1") (pin "15") (pinfunction "2_15") (pintype "input"))
    )
    (net (code "120") (name "ROW3-2") (class "Default")
      (node (ref "D16") (pin "1") (pinfunction "C_1") (pintype "passive"))
      (node (ref "D17") (pin "1") (pinfunction "C_1") (pintype "passive"))
      (node (ref "D18") (pin "1") (pinfunction "C_1") (pintype "passive"))
      (node (ref "MUX/DEMUX1") (pin "2") (pinfunction "6_2") (pintype "input"))
    )
    (net (code "121") (name "ROWS") (class "Default")
      (node (ref "B1") (pin "D2") (pinfunction "D2_D2") (pintype "bidirectional"))
      (node (ref "MUX/DEMUX1") (pin "3") (pinfunction "COM_3") (pintype "input"))
    )
    (net (code "122") (name "SCK") (class "Default")
      (node (ref "B1") (pin "D13") (pinfunction "D13_D13") (pintype "bidirectional"))
      (node (ref "DRIVER1") (pin "13") (pinfunction "CLK_13") (pintype "bidirectional"))
    )
    (net (code "123") (name "SEL_COL-A") (class "Default")
      (node (ref "B1") (pin "D7") (pinfunction "D7_D7") (pintype "bidirectional"))
      (node (ref "MULT1") (pin "11") (pinfunction "A_11") (pintype "input"))
    )
    (net (code "124") (name "SEL_COL-B") (class "Default")
      (node (ref "B1") (pin "D8") (pinfunction "D8_D8") (pintype "bidirectional"))
      (node (ref "MULT1") (pin "10") (pinfunction "B_10") (pintype "input"))
    )
    (net (code "125") (name "SEL_COL-C") (class "Default")
      (node (ref "B1") (pin "D9") (pinfunction "*D9_D9") (pintype "bidirectional"))
      (node (ref "L20") (pin "2") (pinfunction "A_2") (pintype "passive"))
      (node (ref "MULT1") (pin "9") (pinfunction "C_9") (pintype "input"))
      (node (ref "R91") (pin "1") (pinfunction "1_1") (pintype "passive"))
    )
    (net (code "126") (name "SEL_ROW-A") (class "Default")
      (node (ref "B1") (pin "D3") (pinfunction "*D3_D3") (pintype "bidirectional"))
      (node (ref "MUX/DEMUX1") (pin "11") (pinfunction "A_11") (pintype "input"))
    )
    (net (code "127") (name "SEL_ROW-B") (class "Default")
      (node (ref "B1") (pin "D4") (pinfunction "D4_D4") (pintype "bidirectional"))
      (node (ref "MUX/DEMUX1") (pin "10") (pinfunction "B_10") (pintype "input"))
    )
    (net (code "128") (name "SEL_ROW-C") (class "Default")
      (node (ref "B1") (pin "D5") (pinfunction "*D5_D5") (pintype "bidirectional"))
      (node (ref "MUX/DEMUX1") (pin "9") (pinfunction "C_9") (pintype "input"))
    )
    (net (code "129") (name "VCC") (class "Default")
      (node (ref "C19") (pin "1") (pinfunction "1_1") (pintype "passive"))
      (node (ref "C20") (pin "2") (pinfunction "2_2") (pintype "passive"))
      (node (ref "C21") (pin "2") (pinfunction "2_2") (pintype "passive"))
      (node (ref "DRIVER1") (pin "19") (pinfunction "V+_19") (pintype "power_in"))
      (node (ref "JP1") (pin "2") (pinfunction "2_2") (pintype "passive"))
      (node (ref "L1") (pin "2") (pinfunction "A_2") (pintype "passive"))
      (node (ref "L10") (pin "2") (pinfunction "A_2") (pintype "passive"))
      (node (ref "L11") (pin "2") (pinfunction "A_2") (pintype "passive"))
      (node (ref "L12") (pin "2") (pinfunction "A_2") (pintype "passive"))
      (node (ref "L13") (pin "2") (pinfunction "A_2") (pintype "passive"))
      (node (ref "L14") (pin "2") (pinfunction "A_2") (pintype "passive"))
      (node (ref "L15") (pin "2") (pinfunction "A_2") (pintype "passive"))
      (node (ref "L16") (pin "2") (pinfunction "A_2") (pintype "passive"))
      (node (ref "L17") (pin "2") (pinfunction "A_2") (pintype "passive"))
      (node (ref "L18") (pin "2") (pinfunction "A_2") (pintype "passive"))
      (node (ref "L19") (pin "2") (pinfunction "A_2") (pintype "passive"))
      (node (ref "L2") (pin "2") (pinfunction "A_2") (pintype "passive"))
      (node (ref "L3") (pin "2") (pinfunction "A_2") (pintype "passive"))
      (node (ref "L4") (pin "2") (pinfunction "A_2") (pintype "passive"))
      (node (ref "L5") (pin "2") (pinfunction "A_2") (pintype "passive"))
      (node (ref "L6") (pin "2") (pinfunction "A_2") (pintype "passive"))
      (node (ref "L7") (pin "2") (pinfunction "A_2") (pintype "passive"))
      (node (ref "L8") (pin "2") (pinfunction "A_2") (pintype "passive"))
      (node (ref "L9") (pin "2") (pinfunction "A_2") (pintype "passive"))
      (node (ref "MULT1") (pin "16") (pinfunction "VCC_16") (pintype "power_in"))
      (node (ref "MUX/DEMUX1") (pin "16") (pinfunction "VCC_16") (pintype "power_in"))
      (node (ref "R93") (pin "2") (pinfunction "2_2") (pintype "passive"))
    )
    (net (code "130") (name "unconnected-(B1-*D10-PadD10)") (class "Default")
      (node (ref "B1") (pin "D10") (pinfunction "*D10_D10") (pintype "bidirectional"))
    )
    (net (code "131") (name "unconnected-(B1-*D11-PadD11)") (class "Default")
      (node (ref "B1") (pin "D11") (pinfunction "*D11_D11") (pintype "bidirectional"))
    )
    (net (code "132") (name "unconnected-(B1-Pad3.3V)") (class "Default")
      (node (ref "B1") (pin "3.3V") (pinfunction "3.3V_3.3V") (pintype "bidirectional"))
    )
    (net (code "133") (name "unconnected-(B1-PadA0)") (class "Default")
      (node (ref "B1") (pin "A0") (pinfunction "A0_A0") (pintype "bidirectional"))
    )
    (net (code "134") (name "unconnected-(B1-PadA1)") (class "Default")
      (node (ref "B1") (pin "A1") (pinfunction "A1_A1") (pintype "bidirectional"))
    )
    (net (code "135") (name "unconnected-(B1-PadA2)") (class "Default")
      (node (ref "B1") (pin "A2") (pinfunction "A2_A2") (pintype "bidirectional"))
    )
    (net (code "136") (name "unconnected-(B1-PadA3)") (class "Default")
      (node (ref "B1") (pin "A3") (pinfunction "A3_A3") (pintype "bidirectional"))
    )
    (net (code "137") (name "unconnected-(B1-PadA4)") (class "Default")
      (node (ref "B1") (pin "A4") (pinfunction "A4_A4") (pintype "bidirectional"))
    )
    (net (code "138") (name "unconnected-(B1-PadAREF)") (class "Default")
      (node (ref "B1") (pin "AREF") (pinfunction "AREF_AREF") (pintype "bidirectional"))
    )
    (net (code "139") (name "unconnected-(B1-PadIOREF)") (class "Default")
      (node (ref "B1") (pin "IOREF") (pinfunction "IOREF_IOREF") (pintype "bidirectional"))
    )
    (net (code "140") (name "unconnected-(B1-PadRES)") (class "Default")
      (node (ref "B1") (pin "RES") (pinfunction "RES_RES") (pintype "bidirectional"))
    )
    (net (code "141") (name "unconnected-(B1-PadRX)") (class "Default")
      (node (ref "B1") (pin "RX") (pinfunction "RX_RX") (pintype "bidirectional"))
    )
    (net (code "142") (name "unconnected-(B1-PadSCL)") (class "Default")
      (node (ref "B1") (pin "SCL") (pinfunction "SCL_SCL") (pintype "bidirectional"))
    )
    (net (code "143") (name "unconnected-(B1-PadSDA)") (class "Default")
      (node (ref "B1") (pin "SDA") (pinfunction "SDA_SDA") (pintype "bidirectional"))
    )
    (net (code "144") (name "unconnected-(B1-PadTX)") (class "Default")
      (node (ref "B1") (pin "TX") (pinfunction "TX_TX") (pintype "bidirectional"))
    )
    (net (code "145") (name "unconnected-(B1-PadVIN)") (class "Default")
      (node (ref "B1") (pin "VIN") (pinfunction "VIN_VIN") (pintype "bidirectional"))
    )
    (net (code "146") (name "unconnected-(DRIVER1-DIG3-Pad7)") (class "Default")
      (node (ref "DRIVER1") (pin "7") (pinfunction "DIG3_7") (pintype "bidirectional"))
    )
    (net (code "147") (name "unconnected-(DRIVER1-DIG4-Pad3)") (class "Default")
      (node (ref "DRIVER1") (pin "3") (pinfunction "DIG4_3") (pintype "bidirectional"))
    )
    (net (code "148") (name "unconnected-(DRIVER1-DIG5-Pad10)") (class "Default")
      (node (ref "DRIVER1") (pin "10") (pinfunction "DIG5_10") (pintype "bidirectional"))
    )
    (net (code "149") (name "unconnected-(DRIVER1-DIG6-Pad5)") (class "Default")
      (node (ref "DRIVER1") (pin "5") (pinfunction "DIG6_5") (pintype "bidirectional"))
    )
    (net (code "150") (name "unconnected-(DRIVER1-DIG7-Pad8)") (class "Default")
      (node (ref "DRIVER1") (pin "8") (pinfunction "DIG7_8") (pintype "bidirectional"))
    )
    (net (code "151") (name "unconnected-(DRIVER1-DOUT-Pad24)") (class "Default")
      (node (ref "DRIVER1") (pin "24") (pinfunction "DOUT_24") (pintype "bidirectional"))
    )
    (net (code "152") (name "unconnected-(DRIVER1-SEGDP-Pad22)") (class "Default")
      (node (ref "DRIVER1") (pin "22") (pinfunction "SEGDP_22") (pintype "bidirectional"))
    )
    (net (code "153") (name "unconnected-(DRIVER1-SEGG-Pad17)") (class "Default")
      (node (ref "DRIVER1") (pin "17") (pinfunction "SEGG_17") (pintype "bidirectional"))
    )
    (net (code "154") (name "unconnected-(MULT1-W-Pad6)") (class "Default")
      (node (ref "MULT1") (pin "6") (pinfunction "W_6") (pintype "output"))
    )
  )
)
